# STM32_SIM800C.net
KiCad netlist of a schematic drawn in Altium Designer
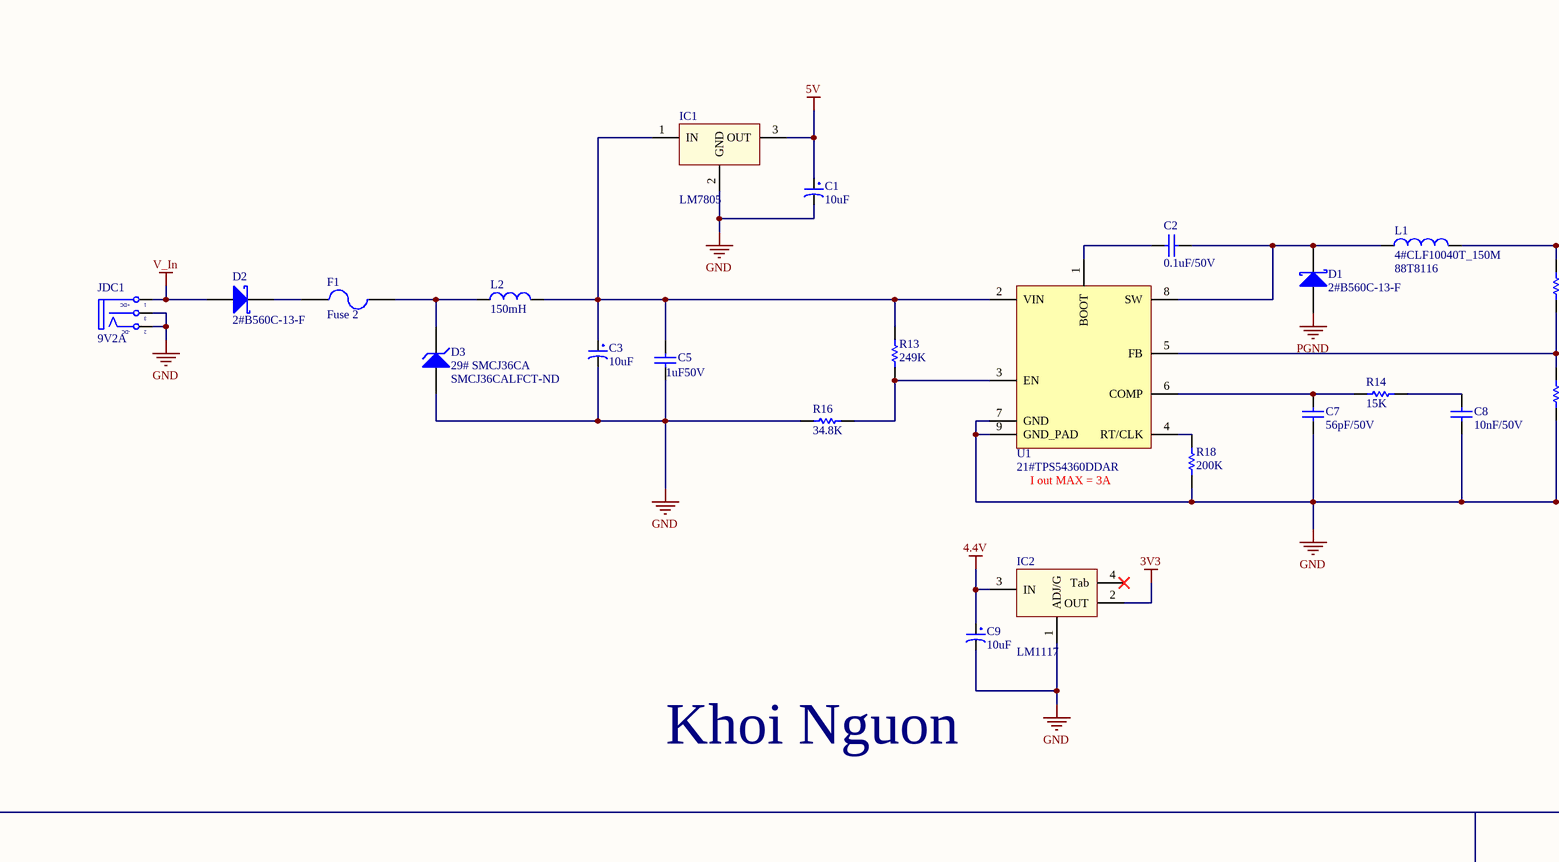
[diagram p0: STM32_SIM800C.SchDoc, top left]
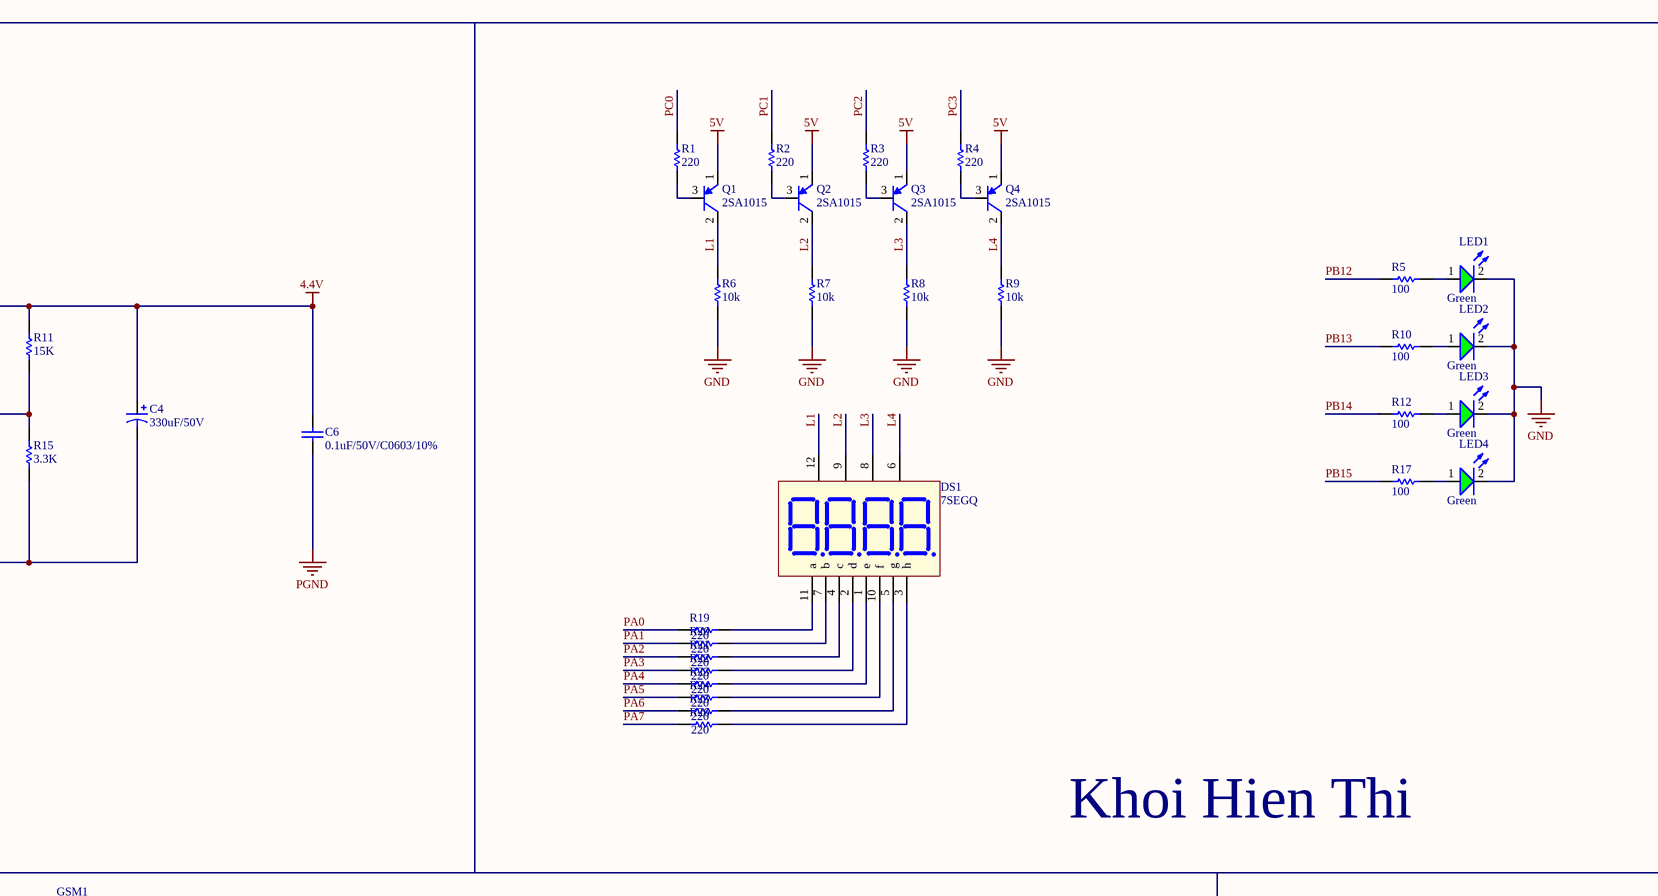
[diagram p1: STM32_SIM800C.SchDoc, top right]
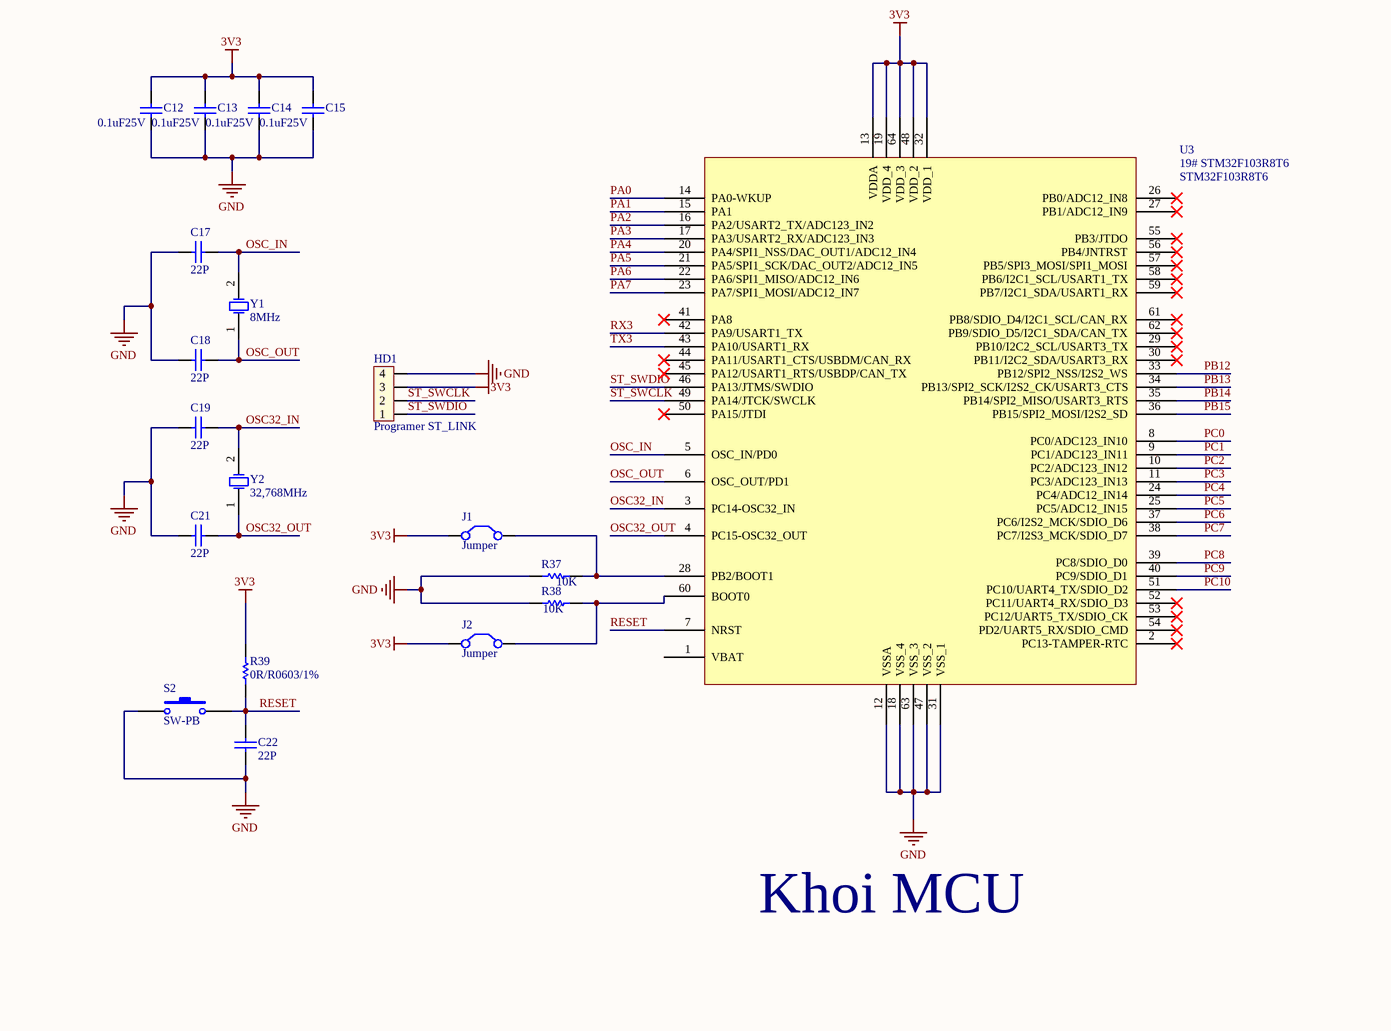
[diagram p2: STM32_SIM800C.SchDoc, bottom left]
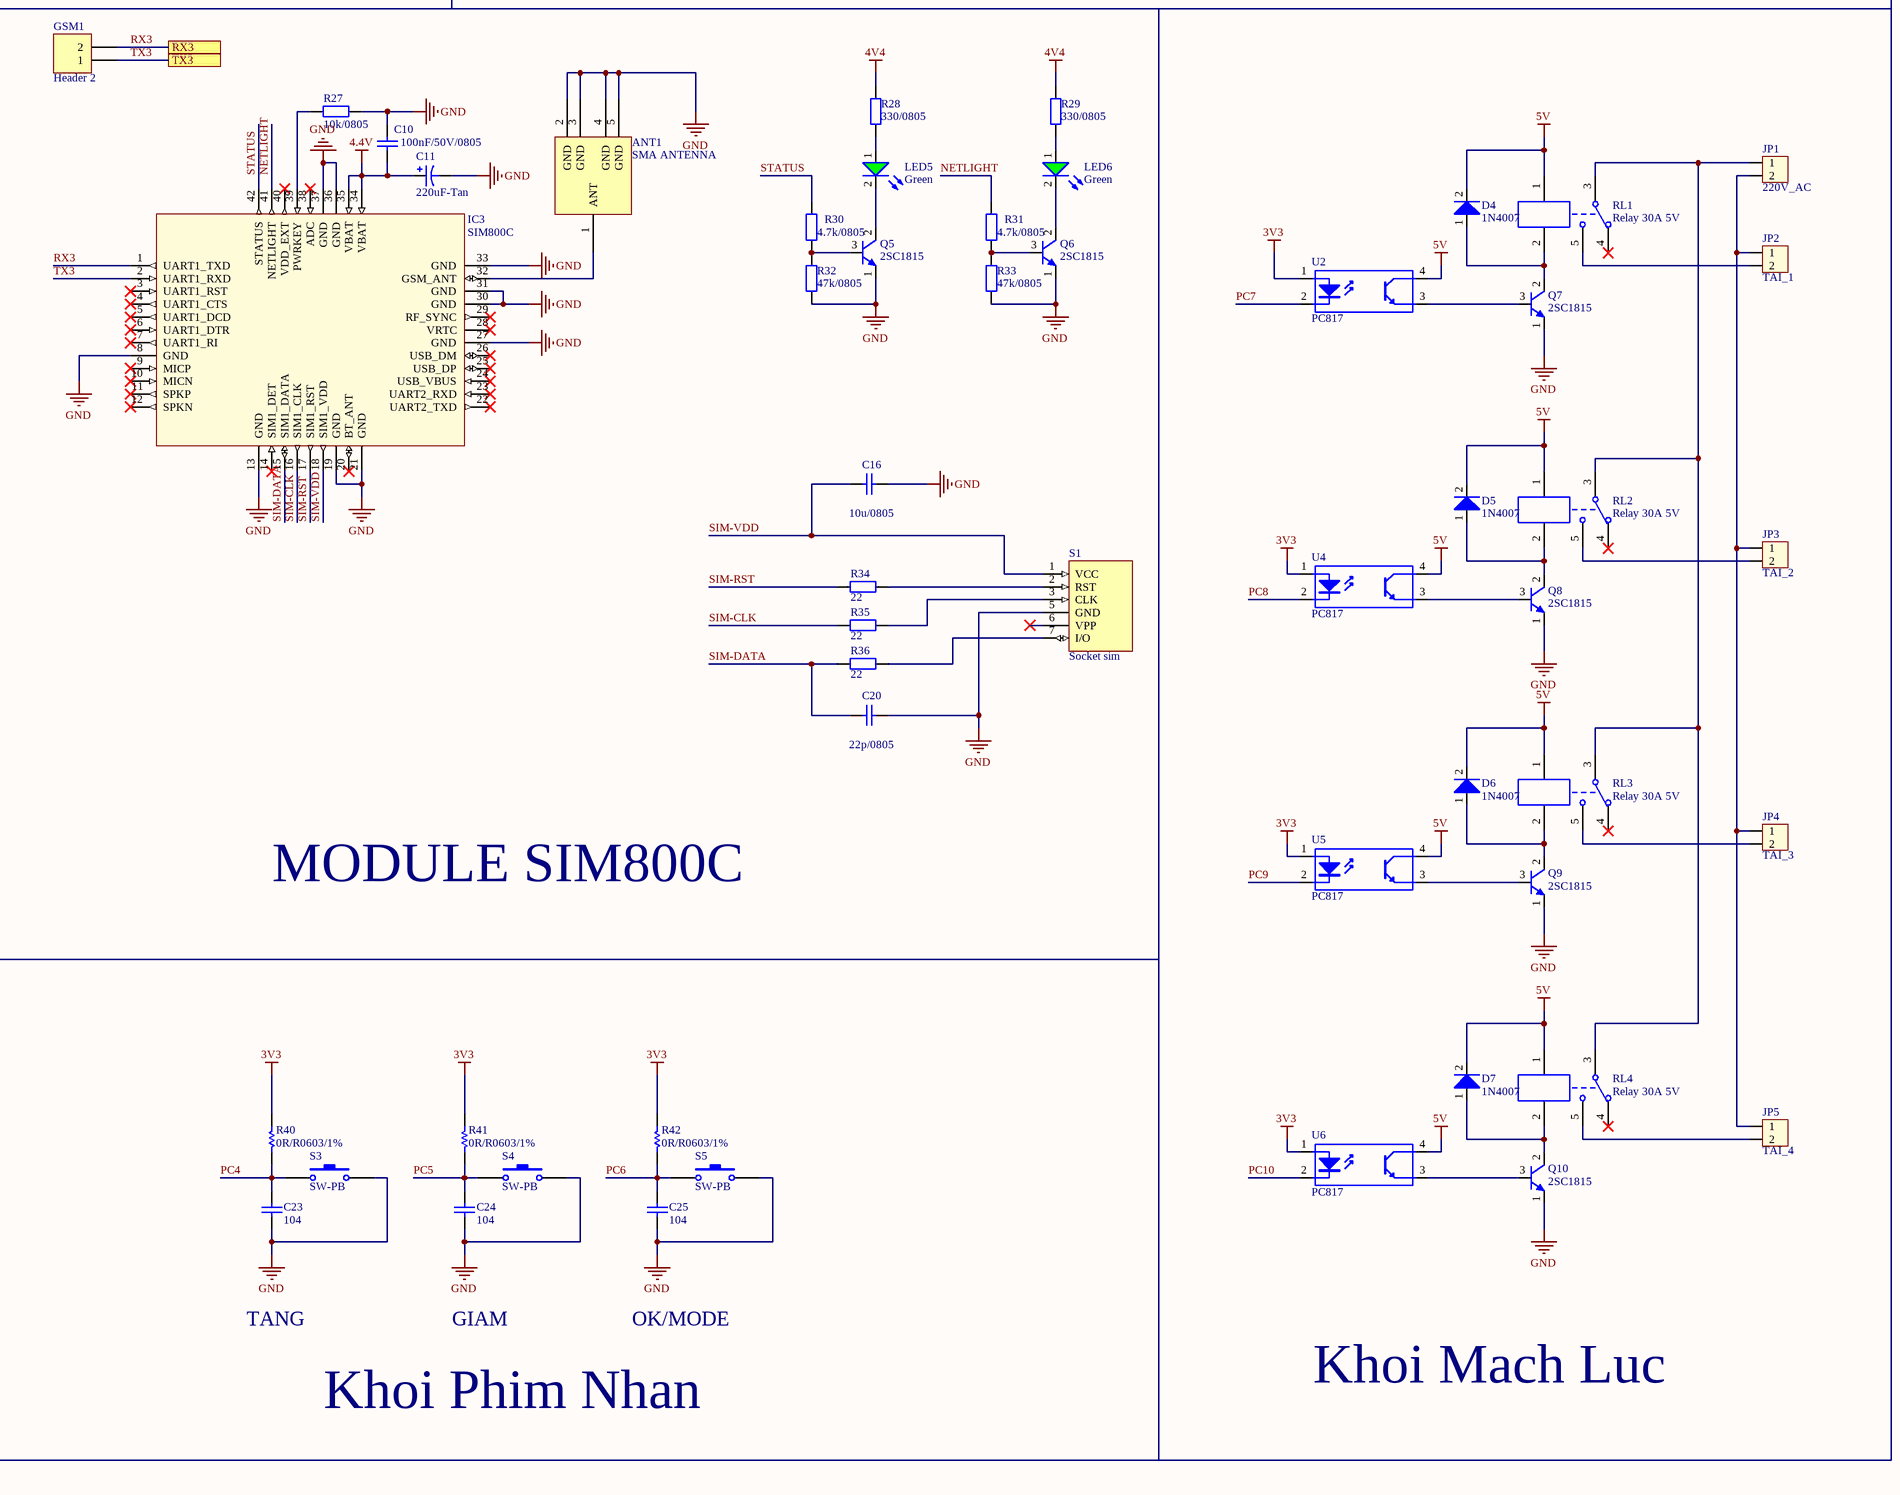
[diagram p3: STM32_SIM800C.SchDoc, bottom right]

(export (version "E")
  (design (tool "Eeschema 10.0.6"))
  (components
    (comp (ref "ANT1")
      (value "SMA ANTENNA")
      (footprint "du an mau 1:ANT-SMA-ST-F")
      (libsource (lib "Air_System_lib") (part "SMA ANTENNA"))
    )
    (comp (ref "C1")
      (value "10uF")
      (footprint "CP1/2")
      (description "Cap P  0,1uF < 22uF , 16 - 50V")
      (libsource (lib "lpson") (part "CP1"))
    )
    (comp (ref "C2")
      (value "0.1uF/50V")
      (footprint "Cap Ceramic 0603 SMD")
      (description "CAP CER 0.1UF 50V 10% X7R 0603")
      (fields
        (field (name "MANUFACTURER") "Murata Electronics North America")
        (field (name "MANUFACTURER PART NUMBER") "GRM188R71H104KA93D")
      )
      (libsource (lib "GSHT_181013") (part "0.1uF/50V/C0603/10%"))
    )
    (comp (ref "C3")
      (value "10uF")
      (footprint "CP1/2")
      (description "Cap P  0,1uF < 22uF , 16 - 50V")
      (libsource (lib "lpson") (part "CP1"))
    )
    (comp (ref "C4")
      (value "330uF/50V")
      (footprint "CAP ALU CASE G SMD")
      (description "CAP ALU 330UF 20% 50V SMD")
      (fields
        (field (name "MANUFACTURER") "Nichicon")
        (field (name "MANUFACTURER PART NUMBER") "UPW1J331MHD")
      )
      (libsource (lib "GSHT_181013") (part "330uF/50V/ALU12.5X20mm/20%/7000Hrs"))
    )
    (comp (ref "C5")
      (value "1uF50V")
      (footprint "Cap Ceramic 0603 SMD")
      (description "CAP CER 0.1UF 50V 10% X7R 0603")
      (fields
        (field (name "MANUFACTURER") "Murata Electronics North America")
        (field (name "MANUFACTURER PART NUMBER") "GRM188R71H104KA93D")
      )
      (libsource (lib "lpson") (part "0.1uF/50V/C0603/10%"))
    )
    (comp (ref "C6")
      (value "0.1uF/50V/C0603/10%")
      (footprint "Cap Ceramic 0603 SMD")
      (description "CAP CER 0.1UF 50V 10% X7R 0603")
      (fields
        (field (name "MANUFACTURER") "Murata Electronics North America")
        (field (name "MANUFACTURER PART NUMBER") "GRM188R71H104KA93D")
      )
      (libsource (lib "GSHT_181013") (part "0.1uF/50V/C0603/10%"))
    )
    (comp (ref "C7")
      (value "56pF/50V")
      (footprint "Cap Ceramic 0603 SMD")
      (description "Cap Ceramic 56pF 50V C0G 5% SMD 0603 125C Paper T/R")
      (fields
        (field (name "MANUFACTURER") "Samsung")
        (field (name "MANUFACTURER PART NUMBER") "CL10C560JB8NNNC")
      )
      (libsource (lib "GSHT_181013") (part "56pF/50V/C0603/5%"))
    )
    (comp (ref "C8")
      (value "10nF/50V")
      (footprint "Cap Ceramic 0603 SMD")
      (description "CAP CER 10000PF 50V X7R 0603")
      (fields
        (field (name "MANUFACTURER") "Murata Electronics North America")
        (field (name "MANUFACTURER PART NUMBER") "GRM188R71H103KA01D")
      )
      (libsource (lib "GSHT_181013") (part "10nF/50V/C0603/10%"))
    )
    (comp (ref "C9")
      (value "10uF")
      (footprint "CP1/2")
      (description "Cap P  0,1uF < 22uF , 16 - 50V")
      (libsource (lib "lpson") (part "CP1"))
    )
    (comp (ref "C10")
      (value "100nF/50V/0805")
      (footprint "C0805-2012")
      (fields (field (name "PUBLISHER") "Altium Limited"))
      (libsource (lib "NBBLib 14-03-2012") (part "CapSMD"))
    )
    (comp (ref "C11")
      (value "220uF-Tan")
      (footprint "CAP_TANTA_10UF_35V")
      (libsource (lib "Air_System_lib") (part "CAP1210-Tan"))
    )
    (comp (ref "C12")
      (value "0.1uF25V")
      (footprint "Cap Ceramic 0603 SMD")
      (description "CAP CER 0.1UF 50V 10% X7R 0603")
      (fields
        (field (name "MANUFACTURER") "Murata Electronics North America")
        (field (name "MANUFACTURER PART NUMBER") "GRM188R71H104KA93D")
      )
      (libsource (lib "lpson") (part "0.1uF/50V/C0603/10%"))
    )
    (comp (ref "C13")
      (value "0.1uF25V")
      (footprint "Cap Ceramic 0603 SMD")
      (description "CAP CER 0.1UF 50V 10% X7R 0603")
      (fields
        (field (name "MANUFACTURER") "Murata Electronics North America")
        (field (name "MANUFACTURER PART NUMBER") "GRM188R71H104KA93D")
      )
      (libsource (lib "lpson") (part "0.1uF/50V/C0603/10%"))
    )
    (comp (ref "C14")
      (value "0.1uF25V")
      (footprint "Cap Ceramic 0603 SMD")
      (description "CAP CER 0.1UF 50V 10% X7R 0603")
      (fields
        (field (name "MANUFACTURER") "Murata Electronics North America")
        (field (name "MANUFACTURER PART NUMBER") "GRM188R71H104KA93D")
      )
      (libsource (lib "lpson") (part "0.1uF/50V/C0603/10%"))
    )
    (comp (ref "C15")
      (value "0.1uF25V")
      (footprint "Cap Ceramic 0603 SMD")
      (description "CAP CER 0.1UF 50V 10% X7R 0603")
      (fields
        (field (name "MANUFACTURER") "Murata Electronics North America")
        (field (name "MANUFACTURER PART NUMBER") "GRM188R71H104KA93D")
      )
      (libsource (lib "lpson") (part "0.1uF/50V/C0603/10%"))
    )
    (comp (ref "C16")
      (value "10u/0805")
      (footprint "C0805-2012")
      (description "Capacitor")
      (fields (field (name "PUBLISHER") "Altium Limited"))
      (libsource (lib "NBBLib 14-03-2012") (part "CapSMD"))
    )
    (comp (ref "C17")
      (value "22P")
      (footprint "Cap Ceramic 0603 SMD")
      (description "CAP CER 0.1UF 50V 10% X7R 0603")
      (fields
        (field (name "MANUFACTURER") "Murata Electronics North America")
        (field (name "MANUFACTURER PART NUMBER") "GRM188R71H104KA93D")
      )
      (libsource (lib "lpson") (part "0.1uF/50V/C0603/10%"))
    )
    (comp (ref "C18")
      (value "22P")
      (footprint "Cap Ceramic 0603 SMD")
      (description "CAP CER 0.1UF 50V 10% X7R 0603")
      (fields
        (field (name "MANUFACTURER") "Murata Electronics North America")
        (field (name "MANUFACTURER PART NUMBER") "GRM188R71H104KA93D")
      )
      (libsource (lib "lpson") (part "0.1uF/50V/C0603/10%"))
    )
    (comp (ref "C19")
      (value "22P")
      (footprint "Cap Ceramic 0603 SMD")
      (description "CAP CER 0.1UF 50V 10% X7R 0603")
      (fields
        (field (name "MANUFACTURER") "Murata Electronics North America")
        (field (name "MANUFACTURER PART NUMBER") "GRM188R71H104KA93D")
      )
      (libsource (lib "lpson") (part "0.1uF/50V/C0603/10%"))
    )
    (comp (ref "C20")
      (value "22p/0805")
      (footprint "C0805-2012")
      (description "Capacitor")
      (fields (field (name "PUBLISHER") "Altium Limited"))
      (libsource (lib "NBBLib 14-03-2012") (part "CapSMD"))
    )
    (comp (ref "C21")
      (value "22P")
      (footprint "Cap Ceramic 0603 SMD")
      (description "CAP CER 0.1UF 50V 10% X7R 0603")
      (fields
        (field (name "MANUFACTURER") "Murata Electronics North America")
        (field (name "MANUFACTURER PART NUMBER") "GRM188R71H104KA93D")
      )
      (libsource (lib "lpson") (part "0.1uF/50V/C0603/10%"))
    )
    (comp (ref "C22")
      (value "22P")
      (footprint "Cap Ceramic 0603 SMD")
      (description "CAP CER 0.1UF 50V 10% X7R 0603")
      (fields
        (field (name "MANUFACTURER") "Murata Electronics North America")
        (field (name "MANUFACTURER PART NUMBER") "GRM188R71H104KA93D")
      )
      (libsource (lib "lpson") (part "0.1uF/50V/C0603/10%"))
    )
    (comp (ref "C23")
      (value "104")
      (footprint "Cap Ceramic 0603 SMD")
      (description "CAP CER 0.1UF 50V 10% X7R 0603")
      (fields
        (field (name "MANUFACTURER") "Murata Electronics North America")
        (field (name "MANUFACTURER PART NUMBER") "GRM188R71H104KA93D")
      )
      (libsource (lib "lpson") (part "0.1uF/50V/C0603/10%"))
    )
    (comp (ref "C24")
      (value "104")
      (footprint "Cap Ceramic 0603 SMD")
      (description "CAP CER 0.1UF 50V 10% X7R 0603")
      (fields
        (field (name "MANUFACTURER") "Murata Electronics North America")
        (field (name "MANUFACTURER PART NUMBER") "GRM188R71H104KA93D")
      )
      (libsource (lib "lpson") (part "0.1uF/50V/C0603/10%"))
    )
    (comp (ref "C25")
      (value "104")
      (footprint "Cap Ceramic 0603 SMD")
      (description "CAP CER 0.1UF 50V 10% X7R 0603")
      (fields
        (field (name "MANUFACTURER") "Murata Electronics North America")
        (field (name "MANUFACTURER PART NUMBER") "GRM188R71H104KA93D")
      )
      (libsource (lib "lpson") (part "0.1uF/50V/C0603/10%"))
    )
    (comp (ref "D1")
      (value "2#B560C-13-F")
      (footprint "2# B560C")
      (description "DIODE SCHOTTKY 60V 5A SMC")
      (fields (field (name "MANUFACTURER") "Diodes") (field (name "MANUFACTURER PART NUMBER") "B560C-13-F"))
      (libsource (lib "GSHT_181013") (part "2#B560C-13-F"))
    )
    (comp (ref "D2")
      (value "2#B560C-13-F")
      (footprint "2# B560C")
      (description "DIODE SCHOTTKY 60V 5A SMC")
      (fields (field (name "MANUFACTURER") "Diodes") (field (name "MANUFACTURER PART NUMBER") "B560C-13-F"))
      (libsource (lib "lpson") (part "2#B560C-13-F"))
    )
    (comp (ref "D3")
      (value "29# SMCJ36CA")
      (footprint "29# diode SMCJ36A")
      (description "TVS DIODE 36VWM 58.1VC SMC")
      (fields
        (field (name "MANUFACTURER") "Littelfuse")
        (field (name "MANUFACTURER PART NUMBER") "SMCJ36CA")
        (field (name "SUPPLIER PART NUMBER 1") "SMCJ36CALFCT-ND")
      )
      (libsource (lib "GSHT_181013") (part "29# SMCJ36CA"))
    )
    (comp (ref "D4")
      (value "1N4007")
      (footprint "1N4007")
      (description "Diode LS 1A 1000V DO-41")
      (libsource (lib "lpson") (part "1N4007"))
    )
    (comp (ref "D5")
      (value "1N4007")
      (footprint "1N4007")
      (description "Diode LS 1A 1000V DO-41")
      (libsource (lib "lpson") (part "1N4007"))
    )
    (comp (ref "D6")
      (value "1N4007")
      (footprint "1N4007")
      (description "Diode LS 1A 1000V DO-41")
      (libsource (lib "lpson") (part "1N4007"))
    )
    (comp (ref "D7")
      (value "1N4007")
      (footprint "1N4007")
      (description "Diode LS 1A 1000V DO-41")
      (libsource (lib "lpson") (part "1N4007"))
    )
    (comp (ref "DS1")
      (value "7SEGQ")
      (footprint "7SEGQ")
      (description "Four 7 Seg Dipslay")
      (libsource (lib "lpson") (part "LED7Q"))
    )
    (comp (ref "F1")
      (value "Fuse 2")
      (footprint "PIN-W2/E2.8")
      (description "Fuse")
      (fields (field (name "PUBLISHER") "Altium Limited"))
      (libsource (lib "lpson") (part "Fuse 2"))
    )
    (comp (ref "GSM1")
      (value "Header 2")
      (footprint "Header_2")
      (description "Header, 2-Pin")
      (fields (field (name "PUBLISHER") "Altium Limited"))
      (libsource (lib "NBBLib 14-03-2012") (part "Header 2"))
    )
    (comp (ref "HD1")
      (value "Programer ST_LINK")
      (footprint "Header_4")
      (description "Header 4")
      (libsource (lib "lpson") (part "Header4"))
    )
    (comp (ref "IC1")
      (value "LM7805")
      (footprint "QTO-220")
      (description "On ap +, from + 5 to + 24VDC")
      (libsource (lib "lpson") (part "LM78xx"))
    )
    (comp (ref "IC2")
      (value "LM1117")
      (footprint "SOT223-4N")
      (description "3v3")
      (libsource (lib "lpson") (part "LM1117"))
    )
    (comp (ref "IC3")
      (value "SIM800C")
      (footprint "SIM800C")
      (description "SIM800C V1.00")
      (libsource (lib "LIEMTHANH_LIB") (part "SIM800C"))
    )
    (comp (ref "J1")
      (value "Jumper")
      (footprint "Header_2")
      (description "Jumper Wire")
      (fields (field (name "PUBLISHER") "Altium Limited"))
      (libsource (lib "lpson") (part "Jumper"))
    )
    (comp (ref "J2")
      (value "Jumper")
      (footprint "Header_2")
      (description "Jumper Wire")
      (fields (field (name "PUBLISHER") "Altium Limited"))
      (libsource (lib "lpson") (part "Jumper"))
    )
    (comp (ref "JDC1")
      (value "9V2A")
      (footprint "DC-IN")
      (description "Jac DC input")
      (libsource (lib "lpson") (part "DCIN"))
    )
    (comp (ref "JP1")
      (value "220V_AC")
      (footprint "DOMINO_OSTTC_2P")
      (description "Connector 2")
      (libsource (lib "lpson") (part "Con2_1"))
    )
    (comp (ref "JP2")
      (value "TAI_1")
      (footprint "DOMINO_OSTTC_2P")
      (description "Connector 2")
      (libsource (lib "lpson") (part "Con2_1"))
    )
    (comp (ref "JP3")
      (value "TAI_2")
      (footprint "DOMINO_OSTTC_2P")
      (description "Connector 2")
      (libsource (lib "lpson") (part "Con2_1"))
    )
    (comp (ref "JP4")
      (value "TAI_3")
      (footprint "DOMINO_OSTTC_2P")
      (description "Connector 2")
      (libsource (lib "lpson") (part "Con2_1"))
    )
    (comp (ref "JP5")
      (value "TAI_4")
      (footprint "DOMINO_OSTTC_2P")
      (description "Connector 2")
      (libsource (lib "lpson") (part "Con2_1"))
    )
    (comp (ref "L1")
      (value "4#CLF10040T_150M")
      (footprint "4# clf10040XX")
      (description "FIXED IND 15uH 3.2A 40 MOHM (10.0×9.7×3.8)")
      (fields (field (name "SUPPLIER PART NUMBER 1") "88T8116"))
      (libsource (lib "GSHT_181013") (part "4#CLF10040T_150M"))
    )
    (comp (ref "L2")
      (value "150mH")
      (footprint "L/0.4")
      (description "Inductor")
      (libsource (lib "lpson") (part "L1"))
    )
    (comp (ref "LED1")
      (value "Green")
      (footprint "LED5G")
      (description "LED Green 20mA 2.2V 5mm")
      (fields (field (name "Comment") "LT0054"))
      (libsource (lib "lpson") (part "LT0054"))
    )
    (comp (ref "LED2")
      (value "Green")
      (footprint "LED5G")
      (description "LED Green 20mA 2.2V 5mm")
      (fields (field (name "Comment") "LT0054"))
      (libsource (lib "lpson") (part "LT0054"))
    )
    (comp (ref "LED3")
      (value "Green")
      (footprint "LED5G")
      (description "LED Green 20mA 2.2V 5mm")
      (fields (field (name "Comment") "LT0054"))
      (libsource (lib "lpson") (part "LT0054"))
    )
    (comp (ref "LED4")
      (value "Green")
      (footprint "LED5G")
      (description "LED Green 20mA 2.2V 5mm")
      (fields (field (name "Comment") "LT0054"))
      (libsource (lib "lpson") (part "LT0054"))
    )
    (comp (ref "LED5")
      (value "Green")
      (footprint "LED5G")
      (description "LED Green 20mA 2.2V 5mm")
      (fields (field (name "Comment") "LT0054"))
      (libsource (lib "lpson") (part "LT0054"))
    )
    (comp (ref "LED6")
      (value "Green")
      (footprint "LED5G")
      (description "LED Green 20mA 2.2V 5mm")
      (fields (field (name "Comment") "LT0054"))
      (libsource (lib "lpson") (part "LT0054"))
    )
    (comp (ref "Q1")
      (value "2SA1015")
      (footprint "2SA1015")
      (description "Trans PNP -50V -150mA TO-92")
      (libsource (lib "lpson") (part "2SA1015"))
    )
    (comp (ref "Q2")
      (value "2SA1015")
      (footprint "2SA1015")
      (description "Trans PNP -50V -150mA TO-92")
      (libsource (lib "lpson") (part "2SA1015"))
    )
    (comp (ref "Q3")
      (value "2SA1015")
      (footprint "2SA1015")
      (description "Trans PNP -50V -150mA TO-92")
      (libsource (lib "lpson") (part "2SA1015"))
    )
    (comp (ref "Q4")
      (value "2SA1015")
      (footprint "2SA1015")
      (description "Trans PNP -50V -150mA TO-92")
      (libsource (lib "lpson") (part "2SA1015"))
    )
    (comp (ref "Q5")
      (value "2SC1815")
      (footprint "2SC1815")
      (description "Trans NPN 50V 150mA TO-92")
      (libsource (lib "lpson") (part "2SC1815"))
    )
    (comp (ref "Q6")
      (value "2SC1815")
      (footprint "2SC1815")
      (description "Trans NPN 50V 150mA TO-92")
      (libsource (lib "lpson") (part "2SC1815"))
    )
    (comp (ref "Q7")
      (value "2SC1815")
      (footprint "2SC1815")
      (description "Trans NPN 50V 150mA TO-92")
      (libsource (lib "lpson") (part "2SC1815"))
    )
    (comp (ref "Q8")
      (value "2SC1815")
      (footprint "2SC1815")
      (description "Trans NPN 50V 150mA TO-92")
      (libsource (lib "lpson") (part "2SC1815"))
    )
    (comp (ref "Q9")
      (value "2SC1815")
      (footprint "2SC1815")
      (description "Trans NPN 50V 150mA TO-92")
      (libsource (lib "lpson") (part "2SC1815"))
    )
    (comp (ref "Q10")
      (value "2SC1815")
      (footprint "2SC1815")
      (description "Trans NPN 50V 150mA TO-92")
      (libsource (lib "lpson") (part "2SC1815"))
    )
    (comp (ref "R1")
      (value "220")
      (footprint "Res 0603 SMD")
      (description "RES SMD 10K OHM 1% 1/10W 0603")
      (fields
        (field (name "MANUFACTURER") "Yageo")
        (field (name "MANUFACTURER PART NUMBER") "RC0603FR-0710KL")
      )
      (libsource (lib "lpson") (part "10K/R0603/1%"))
    )
    (comp (ref "R2")
      (value "220")
      (footprint "Res 0603 SMD")
      (description "RES SMD 10K OHM 1% 1/10W 0603")
      (fields
        (field (name "MANUFACTURER") "Yageo")
        (field (name "MANUFACTURER PART NUMBER") "RC0603FR-0710KL")
      )
      (libsource (lib "lpson") (part "10K/R0603/1%"))
    )
    (comp (ref "R3")
      (value "220")
      (footprint "Res 0603 SMD")
      (description "RES SMD 10K OHM 1% 1/10W 0603")
      (fields
        (field (name "MANUFACTURER") "Yageo")
        (field (name "MANUFACTURER PART NUMBER") "RC0603FR-0710KL")
      )
      (libsource (lib "lpson") (part "10K/R0603/1%"))
    )
    (comp (ref "R4")
      (value "220")
      (footprint "Res 0603 SMD")
      (description "RES SMD 10K OHM 1% 1/10W 0603")
      (fields
        (field (name "MANUFACTURER") "Yageo")
        (field (name "MANUFACTURER PART NUMBER") "RC0603FR-0710KL")
      )
      (libsource (lib "lpson") (part "10K/R0603/1%"))
    )
    (comp (ref "R5")
      (value "100")
      (footprint "Res 0603 SMD")
      (description "RES SMD 10K OHM 1% 1/10W 0603")
      (fields
        (field (name "MANUFACTURER") "Yageo")
        (field (name "MANUFACTURER PART NUMBER") "RC0603FR-0710KL")
      )
      (libsource (lib "lpson") (part "10K/R0603/1%"))
    )
    (comp (ref "R6")
      (value "10k")
      (footprint "Res 0603 SMD")
      (description "RES SMD 10K OHM 1% 1/10W 0603")
      (fields
        (field (name "MANUFACTURER") "Yageo")
        (field (name "MANUFACTURER PART NUMBER") "RC0603FR-0710KL")
      )
      (libsource (lib "lpson") (part "10K/R0603/1%"))
    )
    (comp (ref "R7")
      (value "10k")
      (footprint "Res 0603 SMD")
      (description "RES SMD 10K OHM 1% 1/10W 0603")
      (fields
        (field (name "MANUFACTURER") "Yageo")
        (field (name "MANUFACTURER PART NUMBER") "RC0603FR-0710KL")
      )
      (libsource (lib "lpson") (part "10K/R0603/1%"))
    )
    (comp (ref "R8")
      (value "10k")
      (footprint "Res 0603 SMD")
      (description "RES SMD 10K OHM 1% 1/10W 0603")
      (fields
        (field (name "MANUFACTURER") "Yageo")
        (field (name "MANUFACTURER PART NUMBER") "RC0603FR-0710KL")
      )
      (libsource (lib "lpson") (part "10K/R0603/1%"))
    )
    (comp (ref "R9")
      (value "10k")
      (footprint "Res 0603 SMD")
      (description "RES SMD 10K OHM 1% 1/10W 0603")
      (fields
        (field (name "MANUFACTURER") "Yageo")
        (field (name "MANUFACTURER PART NUMBER") "RC0603FR-0710KL")
      )
      (libsource (lib "lpson") (part "10K/R0603/1%"))
    )
    (comp (ref "R10")
      (value "100")
      (footprint "Res 0603 SMD")
      (description "RES SMD 10K OHM 1% 1/10W 0603")
      (fields
        (field (name "MANUFACTURER") "Yageo")
        (field (name "MANUFACTURER PART NUMBER") "RC0603FR-0710KL")
      )
      (libsource (lib "lpson") (part "10K/R0603/1%"))
    )
    (comp (ref "R11")
      (value "15K")
      (footprint "Res 0603 SMD")
      (description "RES SMD 15K OHM 1% 1/10W 0603")
      (fields
        (field (name "MANUFACTURER") "Yageo")
        (field (name "MANUFACTURER PART NUMBER") "RC0603FR-0715KL")
      )
      (libsource (lib "GSHT_181013") (part "15K/R0603/1%"))
    )
    (comp (ref "R12")
      (value "100")
      (footprint "Res 0603 SMD")
      (description "RES SMD 10K OHM 1% 1/10W 0603")
      (fields
        (field (name "MANUFACTURER") "Yageo")
        (field (name "MANUFACTURER PART NUMBER") "RC0603FR-0710KL")
      )
      (libsource (lib "lpson") (part "10K/R0603/1%"))
    )
    (comp (ref "R13")
      (value "249K")
      (footprint "Res 0805 SMD")
      (description "RES SMD 249K OHM 1% 1/10W 0805")
      (fields
        (field (name "MANUFACTURER") "Yageo")
        (field (name "MANUFACTURER PART NUMBER") "RC0603FR-07249KL")
      )
      (libsource (lib "GSHT_181013") (part "249K/R0805/1%"))
    )
    (comp (ref "R14")
      (value "15K")
      (footprint "Res 0603 SMD")
      (description "RES SMD 15K OHM 1% 1/10W 0603")
      (fields
        (field (name "MANUFACTURER") "Yageo")
        (field (name "MANUFACTURER PART NUMBER") "RC0603FR-0715KL")
      )
      (libsource (lib "GSHT_181013") (part "15K/R0603/1%"))
    )
    (comp (ref "R15")
      (value "3.3K")
      (footprint "Cap Ceramic 0603 SMD")
      (description "RES SMD 3.3K OHM 1% 1/10W 0603")
      (fields
        (field (name "MANUFACTURER") "Yageo")
        (field (name "MANUFACTURER PART NUMBER") "RC0603FR-073K3L")
      )
      (libsource (lib "GSHT_181013") (part "3.3K/R0603/1%"))
    )
    (comp (ref "R16")
      (value "34.8K")
      (footprint "Res 0805 SMD")
      (description "Thick Film Resistors - SMD 34.8K OHM 1% 0805")
      (fields
        (field (name "MANUFACTURER") "Yageo")
        (field (name "MANUFACTURER PART NUMBER") "RC0603FR-0734K8L")
      )
      (libsource (lib "GSHT_181013") (part "34.8K/R0805/1%"))
    )
    (comp (ref "R17")
      (value "100")
      (footprint "Res 0603 SMD")
      (description "RES SMD 10K OHM 1% 1/10W 0603")
      (fields
        (field (name "MANUFACTURER") "Yageo")
        (field (name "MANUFACTURER PART NUMBER") "RC0603FR-0710KL")
      )
      (libsource (lib "lpson") (part "10K/R0603/1%"))
    )
    (comp (ref "R18")
      (value "200K")
      (footprint "Res 0603 SMD")
      (description "RES SMD 200K OHM 1% 1/10W 0603")
      (fields
        (field (name "MANUFACTURER") "Yageo")
        (field (name "MANUFACTURER PART NUMBER") "RC0603FR-07200KL")
      )
      (libsource (lib "GSHT_181013") (part "200K/R0603/1%"))
    )
    (comp (ref "R19")
      (value "220")
      (footprint "Res 0603 SMD")
      (description "RES SMD 10K OHM 1% 1/10W 0603")
      (fields
        (field (name "MANUFACTURER") "Yageo")
        (field (name "MANUFACTURER PART NUMBER") "RC0603FR-0710KL")
      )
      (libsource (lib "lpson") (part "10K/R0603/1%"))
    )
    (comp (ref "R20")
      (value "220")
      (footprint "Res 0603 SMD")
      (description "RES SMD 10K OHM 1% 1/10W 0603")
      (fields
        (field (name "MANUFACTURER") "Yageo")
        (field (name "MANUFACTURER PART NUMBER") "RC0603FR-0710KL")
      )
      (libsource (lib "lpson") (part "10K/R0603/1%"))
    )
    (comp (ref "R21")
      (value "220")
      (footprint "Res 0603 SMD")
      (description "RES SMD 10K OHM 1% 1/10W 0603")
      (fields
        (field (name "MANUFACTURER") "Yageo")
        (field (name "MANUFACTURER PART NUMBER") "RC0603FR-0710KL")
      )
      (libsource (lib "lpson") (part "10K/R0603/1%"))
    )
    (comp (ref "R22")
      (value "220")
      (footprint "Res 0603 SMD")
      (description "RES SMD 10K OHM 1% 1/10W 0603")
      (fields
        (field (name "MANUFACTURER") "Yageo")
        (field (name "MANUFACTURER PART NUMBER") "RC0603FR-0710KL")
      )
      (libsource (lib "lpson") (part "10K/R0603/1%"))
    )
    (comp (ref "R23")
      (value "220")
      (footprint "Res 0603 SMD")
      (description "RES SMD 10K OHM 1% 1/10W 0603")
      (fields
        (field (name "MANUFACTURER") "Yageo")
        (field (name "MANUFACTURER PART NUMBER") "RC0603FR-0710KL")
      )
      (libsource (lib "lpson") (part "10K/R0603/1%"))
    )
    (comp (ref "R24")
      (value "220")
      (footprint "Res 0603 SMD")
      (description "RES SMD 10K OHM 1% 1/10W 0603")
      (fields
        (field (name "MANUFACTURER") "Yageo")
        (field (name "MANUFACTURER PART NUMBER") "RC0603FR-0710KL")
      )
      (libsource (lib "lpson") (part "10K/R0603/1%"))
    )
    (comp (ref "R25")
      (value "220")
      (footprint "Res 0603 SMD")
      (description "RES SMD 10K OHM 1% 1/10W 0603")
      (fields
        (field (name "MANUFACTURER") "Yageo")
        (field (name "MANUFACTURER PART NUMBER") "RC0603FR-0710KL")
      )
      (libsource (lib "lpson") (part "10K/R0603/1%"))
    )
    (comp (ref "R26")
      (value "220")
      (footprint "Res 0603 SMD")
      (description "RES SMD 10K OHM 1% 1/10W 0603")
      (fields
        (field (name "MANUFACTURER") "Yageo")
        (field (name "MANUFACTURER PART NUMBER") "RC0603FR-0710KL")
      )
      (libsource (lib "lpson") (part "10K/R0603/1%"))
    )
    (comp (ref "R27")
      (value "10k/0805")
      (footprint "RESC2012(0805)")
      (description "Resistor SMD 0805")
      (fields (field (name "PUBLISHER") "Altium Limited"))
      (libsource (lib "NBBLib 14-03-2012") (part "R0805"))
    )
    (comp (ref "R28")
      (value "330/0805")
      (footprint "RESC2012(0805)")
      (description "Resistor SMD 0805")
      (fields (field (name "Comment") "R0805") (field (name "PUBLISHER") "Altium Limited"))
      (libsource (lib "") (part "R0805_1"))
    )
    (comp (ref "R29")
      (value "330/0805")
      (footprint "RESC2012(0805)")
      (description "Resistor SMD 0805")
      (fields (field (name "Comment") "R0805") (field (name "PUBLISHER") "Altium Limited"))
      (libsource (lib "") (part "R0805_1"))
    )
    (comp (ref "R30")
      (value "4.7k/0805")
      (footprint "RESC2012(0805)")
      (description "Resistor SMD 0805")
      (fields (field (name "Comment") "R0805") (field (name "PUBLISHER") "Altium Limited"))
      (libsource (lib "") (part "R0805_1"))
    )
    (comp (ref "R31")
      (value "4.7k/0805")
      (footprint "RESC2012(0805)")
      (description "Resistor SMD 0805")
      (fields (field (name "Comment") "R0805") (field (name "PUBLISHER") "Altium Limited"))
      (libsource (lib "") (part "R0805_1"))
    )
    (comp (ref "R32")
      (value "47k/0805")
      (footprint "RESC2012(0805)")
      (description "Resistor SMD 0805")
      (fields (field (name "Comment") "R0805") (field (name "PUBLISHER") "Altium Limited"))
      (libsource (lib "") (part "R0805_1"))
    )
    (comp (ref "R33")
      (value "47k/0805")
      (footprint "RESC2012(0805)")
      (description "Resistor SMD 0805")
      (fields (field (name "Comment") "R0805") (field (name "PUBLISHER") "Altium Limited"))
      (libsource (lib "") (part "R0805_1"))
    )
    (comp (ref "R34")
      (value "22")
      (footprint "RESC2012(0805)")
      (description "Resistor SMD 0805")
      (fields (field (name "Comment") "R0805") (field (name "PUBLISHER") "Altium Limited"))
      (libsource (lib "NBBLib 14-03-2012") (part "R0805"))
    )
    (comp (ref "R35")
      (value "22")
      (footprint "RESC2012(0805)")
      (description "Resistor SMD 0805")
      (fields (field (name "Comment") "R0805") (field (name "PUBLISHER") "Altium Limited"))
      (libsource (lib "NBBLib 14-03-2012") (part "R0805"))
    )
    (comp (ref "R36")
      (value "22")
      (footprint "RESC2012(0805)")
      (description "Resistor SMD 0805")
      (fields (field (name "Comment") "R0805") (field (name "PUBLISHER") "Altium Limited"))
      (libsource (lib "NBBLib 14-03-2012") (part "R0805"))
    )
    (comp (ref "R37")
      (value "10K")
      (footprint "Res 0603 SMD")
      (description "RES SMD 10K OHM 1% 1/10W 0603")
      (fields
        (field (name "MANUFACTURER") "Yageo")
        (field (name "MANUFACTURER PART NUMBER") "RC0603FR-0710KL")
      )
      (libsource (lib "lpson") (part "10K/R0603/1%"))
    )
    (comp (ref "R38")
      (value "10K")
      (footprint "Res 0603 SMD")
      (description "RES SMD 10K OHM 1% 1/10W 0603")
      (fields
        (field (name "MANUFACTURER") "Yageo")
        (field (name "MANUFACTURER PART NUMBER") "RC0603FR-0710KL")
      )
      (libsource (lib "lpson") (part "10K/R0603/1%"))
    )
    (comp (ref "R39")
      (value "0R/R0603/1%")
      (footprint "Res 0603 SMD")
      (description "RES SMD 10K OHM 1% 1/10W 0603")
      (fields
        (field (name "MANUFACTURER") "Yageo")
        (field (name "MANUFACTURER PART NUMBER") "RC0603FR-0710KL")
      )
      (libsource (lib "lpson") (part "10K/R0603/1%"))
    )
    (comp (ref "R40")
      (value "0R/R0603/1%")
      (footprint "Res 0603 SMD")
      (description "RES SMD 10K OHM 1% 1/10W 0603")
      (fields
        (field (name "MANUFACTURER") "Yageo")
        (field (name "MANUFACTURER PART NUMBER") "RC0603FR-0710KL")
      )
      (libsource (lib "lpson") (part "10K/R0603/1%"))
    )
    (comp (ref "R41")
      (value "0R/R0603/1%")
      (footprint "Res 0603 SMD")
      (description "RES SMD 10K OHM 1% 1/10W 0603")
      (fields
        (field (name "MANUFACTURER") "Yageo")
        (field (name "MANUFACTURER PART NUMBER") "RC0603FR-0710KL")
      )
      (libsource (lib "lpson") (part "10K/R0603/1%"))
    )
    (comp (ref "R42")
      (value "0R/R0603/1%")
      (footprint "Res 0603 SMD")
      (description "RES SMD 10K OHM 1% 1/10W 0603")
      (fields
        (field (name "MANUFACTURER") "Yageo")
        (field (name "MANUFACTURER PART NUMBER") "RC0603FR-0710KL")
      )
      (libsource (lib "lpson") (part "10K/R0603/1%"))
    )
    (comp (ref "RL1")
      (value "Relay 30A 5V")
      (footprint "RL_5V_30A")
      (description "Single-Pole Dual-Throw Relay")
      (fields (field (name "PUBLISHER") "Altium Limited"))
      (libsource (lib "lpson") (part "Relay T9GV5L14-5 30A 5V"))
    )
    (comp (ref "RL2")
      (value "Relay 30A 5V")
      (footprint "RL_5V_30A")
      (description "Single-Pole Dual-Throw Relay")
      (fields (field (name "PUBLISHER") "Altium Limited"))
      (libsource (lib "lpson") (part "Relay T9GV5L14-5 30A 5V"))
    )
    (comp (ref "RL3")
      (value "Relay 30A 5V")
      (footprint "RL_5V_30A")
      (description "Single-Pole Dual-Throw Relay")
      (fields (field (name "PUBLISHER") "Altium Limited"))
      (libsource (lib "lpson") (part "Relay T9GV5L14-5 30A 5V"))
    )
    (comp (ref "RL4")
      (value "Relay 30A 5V")
      (footprint "RL_5V_30A")
      (description "Single-Pole Dual-Throw Relay")
      (fields (field (name "PUBLISHER") "Altium Limited"))
      (libsource (lib "lpson") (part "Relay T9GV5L14-5 30A 5V"))
    )
    (comp (ref "S1")
      (value "Socket sim")
      (footprint "Card Sim")
      (libsource (lib "Air_System_lib") (part "Socket sim"))
    )
    (comp (ref "S2")
      (value "SW-PB")
      (footprint "SPST-2")
      (description "Switch")
      (fields (field (name "PUBLISHER") "Altium Limited"))
      (libsource (lib "lpson") (part "SW-PB"))
    )
    (comp (ref "S3")
      (value "SW-PB")
      (footprint "SPST-2")
      (description "Switch")
      (fields (field (name "PUBLISHER") "Altium Limited"))
      (libsource (lib "lpson") (part "SW-PB"))
    )
    (comp (ref "S4")
      (value "SW-PB")
      (footprint "SPST-2")
      (description "Switch")
      (fields (field (name "PUBLISHER") "Altium Limited"))
      (libsource (lib "lpson") (part "SW-PB"))
    )
    (comp (ref "S5")
      (value "SW-PB")
      (footprint "SPST-2")
      (description "Switch")
      (fields (field (name "PUBLISHER") "Altium Limited"))
      (libsource (lib "lpson") (part "SW-PB"))
    )
    (comp (ref "U1")
      (value "21#TPS54360DDAR")
      (footprint "21# TPS54360")
      (description "Voltage Regulators - Switching Regulators 60 Vin,3.5 A,SD DC-DC Converter")
      (fields
        (field (name "MANUFACTURER") "Texas Instruments")
        (field (name "MANUFACTURER PART NUMBER") "TPS54360DDAR")
      )
      (libsource (lib "GSHT_181013") (part "21#TPS54360DDAR"))
    )
    (comp (ref "U2")
      (value "PC817")
      (footprint "DIP-4")
      (description "4-Pin Phototransistor Optocoupler")
      (fields (field (name "PUBLISHER") "Altium Limited"))
      (libsource (lib "lpson") (part "Optoisolator1"))
    )
    (comp (ref "U3")
      (value "19# STM32F103R8T6")
      (footprint "19# STMF103R8T6")
      (fields
        (field (name "SUPPLIER PART NUMBER 1") "STM32F103R8T6")
        (field (name "PUBLISHER") "Altium Limited")
      )
      (libsource (lib "GSHT_181013") (part "19# STM32F103R8T6"))
    )
    (comp (ref "U4")
      (value "PC817")
      (footprint "DIP-4")
      (description "4-Pin Phototransistor Optocoupler")
      (fields (field (name "PUBLISHER") "Altium Limited"))
      (libsource (lib "lpson") (part "Optoisolator1"))
    )
    (comp (ref "U5")
      (value "PC817")
      (footprint "DIP-4")
      (description "4-Pin Phototransistor Optocoupler")
      (fields (field (name "PUBLISHER") "Altium Limited"))
      (libsource (lib "lpson") (part "Optoisolator1"))
    )
    (comp (ref "U6")
      (value "PC817")
      (footprint "DIP-4")
      (description "4-Pin Phototransistor Optocoupler")
      (fields (field (name "PUBLISHER") "Altium Limited"))
      (libsource (lib "lpson") (part "Optoisolator1"))
    )
    (comp (ref "Y1")
      (value "8MHz")
      (footprint "CRYSTAL")
      (description "Crystal Oscillator")
      (fields (field (name "PUBLISHER") "Altium Limited"))
      (libsource (lib "lpson") (part "XTAL_12MHz"))
    )
    (comp (ref "Y2")
      (value "32,768MHz")
      (footprint "CRYSTAL")
      (description "Crystal Oscillator")
      (fields (field (name "PUBLISHER") "Altium Limited"))
      (libsource (lib "lpson") (part "XTAL_12MHz"))
    )
  )
  (nets
    (net (code "2") (name "/L1") (class "Default")
      (node (ref "DS1") (pin "12") (pinfunction "V1_12") (pintype "passive"))
      (node (ref "Q1") (pin "2") (pinfunction "C_2") (pintype "passive"))
      (node (ref "R6") (pin "2") (pinfunction "2_2") (pintype "passive"))
    )
    (net (code "3") (name "/L2") (class "Default")
      (node (ref "DS1") (pin "9") (pinfunction "V2_9") (pintype "passive"))
      (node (ref "Q2") (pin "2") (pinfunction "C_2") (pintype "passive"))
      (node (ref "R7") (pin "2") (pinfunction "2_2") (pintype "passive"))
    )
    (net (code "4") (name "/L3") (class "Default")
      (node (ref "DS1") (pin "8") (pinfunction "V3_8") (pintype "passive"))
      (node (ref "Q3") (pin "2") (pinfunction "C_2") (pintype "passive"))
      (node (ref "R8") (pin "2") (pinfunction "2_2") (pintype "passive"))
    )
    (net (code "5") (name "/L4") (class "Default")
      (node (ref "DS1") (pin "6") (pinfunction "V4_6") (pintype "passive"))
      (node (ref "Q4") (pin "2") (pinfunction "C_2") (pintype "passive"))
      (node (ref "R9") (pin "2") (pinfunction "2_2") (pintype "passive"))
    )
    (net (code "6") (name "/NETLIGHT") (class "Default")
      (node (ref "IC3") (pin "41") (pinfunction "NETLIGHT_41") (pintype "output"))
      (node (ref "R31") (pin "1") (pinfunction "1_1") (pintype "passive"))
    )
    (net (code "7") (name "/OSC32_IN") (class "Default")
      (node (ref "C19") (pin "2") (pinfunction "2_2") (pintype "passive"))
      (node (ref "U3") (pin "3") (pinfunction "PC14-OSC32_IN_3") (pintype "passive"))
      (node (ref "Y2") (pin "2") (pinfunction "OSC2_2") (pintype "passive"))
    )
    (net (code "8") (name "/OSC32_OUT") (class "Default")
      (node (ref "C21") (pin "2") (pinfunction "2_2") (pintype "passive"))
      (node (ref "U3") (pin "4") (pinfunction "PC15-OSC32_OUT_4") (pintype "passive"))
      (node (ref "Y2") (pin "1") (pinfunction "OSC1_1") (pintype "passive"))
    )
    (net (code "9") (name "/OSC_IN") (class "Default")
      (node (ref "C17") (pin "2") (pinfunction "2_2") (pintype "passive"))
      (node (ref "U3") (pin "5") (pinfunction "OSC_IN/PD0_5") (pintype "passive"))
      (node (ref "Y1") (pin "2") (pinfunction "OSC2_2") (pintype "passive"))
    )
    (net (code "10") (name "/OSC_OUT") (class "Default")
      (node (ref "C18") (pin "2") (pinfunction "2_2") (pintype "passive"))
      (node (ref "U3") (pin "6") (pinfunction "OSC_OUT/PD1_6") (pintype "passive"))
      (node (ref "Y1") (pin "1") (pinfunction "OSC1_1") (pintype "passive"))
    )
    (net (code "11") (name "/PA0") (class "Default")
      (node (ref "R19") (pin "2") (pinfunction "2_2") (pintype "passive"))
      (node (ref "U3") (pin "14") (pinfunction "PA0-WKUP_14") (pintype "passive"))
    )
    (net (code "12") (name "/PA1") (class "Default")
      (node (ref "R20") (pin "2") (pinfunction "2_2") (pintype "passive"))
      (node (ref "U3") (pin "15") (pinfunction "PA1_15") (pintype "passive"))
    )
    (net (code "13") (name "/PA2") (class "Default")
      (node (ref "R21") (pin "2") (pinfunction "2_2") (pintype "passive"))
      (node (ref "U3") (pin "16") (pinfunction "PA2/USART2_TX/ADC123_IN2_16") (pintype "passive"))
    )
    (net (code "14") (name "/PA3") (class "Default")
      (node (ref "R22") (pin "2") (pinfunction "2_2") (pintype "passive"))
      (node (ref "U3") (pin "17") (pinfunction "PA3/USART2_RX/ADC123_IN3_17") (pintype "passive"))
    )
    (net (code "15") (name "/PA4") (class "Default")
      (node (ref "R23") (pin "2") (pinfunction "2_2") (pintype "passive"))
      (node (ref "U3") (pin "20") (pinfunction "PA4/SPI1_NSS/DAC_OUT1/ADC12_IN4_20") (pintype "passive"))
    )
    (net (code "16") (name "/PA5") (class "Default")
      (node (ref "R24") (pin "2") (pinfunction "2_2") (pintype "passive"))
      (node (ref "U3") (pin "21") (pinfunction "PA5/SPI1_SCK/DAC_OUT2/ADC12_IN5_21") (pintype "passive"))
    )
    (net (code "17") (name "/PA6") (class "Default")
      (node (ref "R25") (pin "2") (pinfunction "2_2") (pintype "passive"))
      (node (ref "U3") (pin "22") (pinfunction "PA6/SPI1_MISO/ADC12_IN6_22") (pintype "passive"))
    )
    (net (code "18") (name "/PA7") (class "Default")
      (node (ref "R26") (pin "2") (pinfunction "2_2") (pintype "passive"))
      (node (ref "U3") (pin "23") (pinfunction "PA7/SPI1_MOSI/ADC12_IN7_23") (pintype "passive"))
    )
    (net (code "19") (name "/PB12") (class "Default")
      (node (ref "R5") (pin "2") (pinfunction "2_2") (pintype "passive"))
      (node (ref "U3") (pin "33") (pinfunction "PB12/SPI2_NSS/I2S2_WS_33") (pintype "passive"))
    )
    (net (code "20") (name "/PB13") (class "Default")
      (node (ref "R10") (pin "2") (pinfunction "2_2") (pintype "passive"))
      (node (ref "U3") (pin "34") (pinfunction "PB13/SPI2_SCK/I2S2_CK/USART3_CTS_34") (pintype "passive"))
    )
    (net (code "21") (name "/PB14") (class "Default")
      (node (ref "R12") (pin "2") (pinfunction "2_2") (pintype "passive"))
      (node (ref "U3") (pin "35") (pinfunction "PB14/SPI2_MISO/USART3_RTS_35") (pintype "passive"))
    )
    (net (code "22") (name "/PB15") (class "Default")
      (node (ref "R17") (pin "2") (pinfunction "2_2") (pintype "passive"))
      (node (ref "U3") (pin "36") (pinfunction "PB15/SPI2_MOSI/I2S2_SD_36") (pintype "passive"))
    )
    (net (code "23") (name "/PC0") (class "Default")
      (node (ref "R1") (pin "2") (pinfunction "2_2") (pintype "passive"))
      (node (ref "U3") (pin "8") (pinfunction "PC0/ADC123_IN10_8") (pintype "passive"))
    )
    (net (code "24") (name "/PC1") (class "Default")
      (node (ref "R2") (pin "2") (pinfunction "2_2") (pintype "passive"))
      (node (ref "U3") (pin "9") (pinfunction "PC1/ADC123_IN11_9") (pintype "passive"))
    )
    (net (code "25") (name "/PC2") (class "Default")
      (node (ref "R3") (pin "2") (pinfunction "2_2") (pintype "passive"))
      (node (ref "U3") (pin "10") (pinfunction "PC2/ADC123_IN12_10") (pintype "passive"))
    )
    (net (code "26") (name "/PC3") (class "Default")
      (node (ref "R4") (pin "2") (pinfunction "2_2") (pintype "passive"))
      (node (ref "U3") (pin "11") (pinfunction "PC3/ADC123_IN13_11") (pintype "passive"))
    )
    (net (code "27") (name "/PC4") (class "Default")
      (node (ref "C23") (pin "2") (pinfunction "2_2") (pintype "passive"))
      (node (ref "R40") (pin "1") (pinfunction "1_1") (pintype "passive"))
      (node (ref "S3") (pin "2") (pinfunction "2_2") (pintype "passive"))
      (node (ref "U3") (pin "24") (pinfunction "PC4/ADC12_IN14_24") (pintype "passive"))
    )
    (net (code "28") (name "/PC5") (class "Default")
      (node (ref "C24") (pin "2") (pinfunction "2_2") (pintype "passive"))
      (node (ref "R41") (pin "1") (pinfunction "1_1") (pintype "passive"))
      (node (ref "S4") (pin "2") (pinfunction "2_2") (pintype "passive"))
      (node (ref "U3") (pin "25") (pinfunction "PC5/ADC12_IN15_25") (pintype "passive"))
    )
    (net (code "29") (name "/PC6") (class "Default")
      (node (ref "C25") (pin "2") (pinfunction "2_2") (pintype "passive"))
      (node (ref "R42") (pin "1") (pinfunction "1_1") (pintype "passive"))
      (node (ref "S5") (pin "2") (pinfunction "2_2") (pintype "passive"))
      (node (ref "U3") (pin "37") (pinfunction "PC6/I2S2_MCK/SDIO_D6_37") (pintype "passive"))
    )
    (net (code "30") (name "/PC7") (class "Default")
      (node (ref "U2") (pin "2") (pinfunction "K_2") (pintype "passive"))
      (node (ref "U3") (pin "38") (pinfunction "PC7/I2S3_MCK/SDIO_D7_38") (pintype "passive"))
    )
    (net (code "31") (name "/PC8") (class "Default")
      (node (ref "U3") (pin "39") (pinfunction "PC8/SDIO_D0_39") (pintype "passive"))
      (node (ref "U4") (pin "2") (pinfunction "K_2") (pintype "passive"))
    )
    (net (code "32") (name "/PC9") (class "Default")
      (node (ref "U3") (pin "40") (pinfunction "PC9/SDIO_D1_40") (pintype "passive"))
      (node (ref "U5") (pin "2") (pinfunction "K_2") (pintype "passive"))
    )
    (net (code "33") (name "/PC10") (class "Default")
      (node (ref "U3") (pin "51") (pinfunction "PC10/UART4_TX/SDIO_D2_51") (pintype "passive"))
      (node (ref "U6") (pin "2") (pinfunction "K_2") (pintype "passive"))
    )
    (net (code "34") (name "/RESET") (class "Default")
      (node (ref "C22") (pin "2") (pinfunction "2_2") (pintype "passive"))
      (node (ref "R39") (pin "1") (pinfunction "1_1") (pintype "passive"))
      (node (ref "S2") (pin "2") (pinfunction "2_2") (pintype "passive"))
      (node (ref "U3") (pin "7") (pinfunction "NRST_7") (pintype "passive"))
    )
    (net (code "35") (name "/RX3") (class "Default")
      (node (ref "GSM1") (pin "2") (pinfunction "2_2") (pintype "passive"))
      (node (ref "IC3") (pin "1") (pinfunction "UART1_TXD_1") (pintype "output"))
      (node (ref "U3") (pin "42") (pinfunction "PA9/USART1_TX_42") (pintype "passive"))
    )
    (net (code "36") (name "/SIM-CLK") (class "Default")
      (node (ref "IC3") (pin "16") (pinfunction "SIM1_CLK_16") (pintype "output"))
      (node (ref "R35") (pin "1") (pinfunction "1_1") (pintype "passive"))
    )
    (net (code "37") (name "/SIM-DATA") (class "Default")
      (node (ref "C20") (pin "1") (pinfunction "1_1") (pintype "passive"))
      (node (ref "IC3") (pin "15") (pinfunction "SIM1_DATA_15") (pintype "bidirectional"))
      (node (ref "R36") (pin "1") (pinfunction "1_1") (pintype "passive"))
    )
    (net (code "38") (name "/SIM-RST") (class "Default")
      (node (ref "IC3") (pin "17") (pinfunction "SIM1_RST_17") (pintype "output"))
      (node (ref "R34") (pin "1") (pinfunction "1_1") (pintype "passive"))
    )
    (net (code "39") (name "/SIM-VDD") (class "Default")
      (node (ref "C16") (pin "1") (pinfunction "1_1") (pintype "passive"))
      (node (ref "IC3") (pin "18") (pinfunction "SIM1_VDD_18") (pintype "output"))
      (node (ref "S1") (pin "1") (pinfunction "VCC_1") (pintype "input"))
    )
    (net (code "40") (name "/STATUS") (class "Default")
      (node (ref "IC3") (pin "42") (pinfunction "STATUS_42") (pintype "output"))
      (node (ref "R30") (pin "1") (pinfunction "1_1") (pintype "passive"))
    )
    (net (code "41") (name "/ST_SWCLK") (class "Default")
      (node (ref "HD1") (pin "2") (pinfunction "2_2") (pintype "passive"))
      (node (ref "U3") (pin "49") (pinfunction "PA14/JTCK/SWCLK_49") (pintype "passive"))
    )
    (net (code "42") (name "/ST_SWDIO") (class "Default")
      (node (ref "HD1") (pin "1") (pinfunction "1_1") (pintype "passive"))
      (node (ref "U3") (pin "46") (pinfunction "PA13/JTMS/SWDIO_46") (pintype "passive"))
    )
    (net (code "43") (name "/TX3") (class "Default")
      (node (ref "GSM1") (pin "1") (pinfunction "1_1") (pintype "passive"))
      (node (ref "IC3") (pin "2") (pinfunction "UART1_RXD_2") (pintype "input"))
      (node (ref "U3") (pin "43") (pinfunction "PA10/USART1_RX_43") (pintype "passive"))
    )
    (net (code "44") (name "3V3") (class "Default")
      (node (ref "C12") (pin "2") (pinfunction "2_2") (pintype "passive"))
      (node (ref "C13") (pin "2") (pinfunction "2_2") (pintype "passive"))
      (node (ref "C14") (pin "2") (pinfunction "2_2") (pintype "passive"))
      (node (ref "C15") (pin "2") (pinfunction "2_2") (pintype "passive"))
      (node (ref "HD1") (pin "3") (pinfunction "3_3") (pintype "passive"))
      (node (ref "IC2") (pin "2") (pinfunction "OUT_2") (pintype "passive"))
      (node (ref "J1") (pin "1") (pinfunction "C1_1") (pintype "passive"))
      (node (ref "J2") (pin "1") (pinfunction "C1_1") (pintype "passive"))
      (node (ref "R39") (pin "2") (pinfunction "2_2") (pintype "passive"))
      (node (ref "R40") (pin "2") (pinfunction "2_2") (pintype "passive"))
      (node (ref "R41") (pin "2") (pinfunction "2_2") (pintype "passive"))
      (node (ref "R42") (pin "2") (pinfunction "2_2") (pintype "passive"))
      (node (ref "U2") (pin "1") (pinfunction "A_1") (pintype "passive"))
      (node (ref "U3") (pin "13") (pinfunction "VDDA_13") (pintype "power_in"))
      (node (ref "U3") (pin "19") (pinfunction "VDD_4_19") (pintype "power_in"))
      (node (ref "U3") (pin "32") (pinfunction "VDD_1_32") (pintype "power_in"))
      (node (ref "U3") (pin "48") (pinfunction "VDD_2_48") (pintype "power_in"))
      (node (ref "U3") (pin "64") (pinfunction "VDD_3_64") (pintype "power_in"))
      (node (ref "U4") (pin "1") (pinfunction "A_1") (pintype "passive"))
      (node (ref "U5") (pin "1") (pinfunction "A_1") (pintype "passive"))
      (node (ref "U6") (pin "1") (pinfunction "A_1") (pintype "passive"))
    )
    (net (code "45") (name "4.4V") (class "Default")
      (node (ref "C10") (pin "1") (pinfunction "1_1") (pintype "passive"))
      (node (ref "C11") (pin "1") (pinfunction "1_1") (pintype "passive"))
      (node (ref "C4") (pin "1") (pinfunction "1_1") (pintype "passive"))
      (node (ref "C6") (pin "2") (pinfunction "2_2") (pintype "passive"))
      (node (ref "C9") (pin "1") (pinfunction "1_1") (pintype "passive"))
      (node (ref "IC2") (pin "3") (pinfunction "IN_3") (pintype "passive"))
      (node (ref "IC3") (pin "34") (pinfunction "VBAT_34") (pintype "input"))
      (node (ref "IC3") (pin "35") (pinfunction "VBAT_35") (pintype "input"))
      (node (ref "L1") (pin "2") (pinfunction "2_2") (pintype "passive"))
      (node (ref "R11") (pin "2") (pinfunction "2_2") (pintype "passive"))
    )
    (net (code "46") (name "4V4") (class "Default")
      (node (ref "R28") (pin "1") (pinfunction "1_1") (pintype "passive"))
      (node (ref "R29") (pin "1") (pinfunction "1_1") (pintype "passive"))
    )
    (net (code "47") (name "5V") (class "Default")
      (node (ref "C1") (pin "1") (pinfunction "1_1") (pintype "passive"))
      (node (ref "D4") (pin "2") (pinfunction "K_2") (pintype "passive"))
      (node (ref "D5") (pin "2") (pinfunction "K_2") (pintype "passive"))
      (node (ref "D6") (pin "2") (pinfunction "K_2") (pintype "passive"))
      (node (ref "D7") (pin "2") (pinfunction "K_2") (pintype "passive"))
      (node (ref "IC1") (pin "3") (pinfunction "OUT_3") (pintype "passive"))
      (node (ref "Q1") (pin "1") (pinfunction "E_1") (pintype "passive"))
      (node (ref "Q2") (pin "1") (pinfunction "E_1") (pintype "passive"))
      (node (ref "Q3") (pin "1") (pinfunction "E_1") (pintype "passive"))
      (node (ref "Q4") (pin "1") (pinfunction "E_1") (pintype "passive"))
      (node (ref "RL1") (pin "1") (pinfunction "1_1") (pintype "passive"))
      (node (ref "RL2") (pin "1") (pinfunction "1_1") (pintype "passive"))
      (node (ref "RL3") (pin "1") (pinfunction "1_1") (pintype "passive"))
      (node (ref "RL4") (pin "1") (pinfunction "1_1") (pintype "passive"))
      (node (ref "U2") (pin "4") (pinfunction "C_4") (pintype "passive"))
      (node (ref "U4") (pin "4") (pinfunction "C_4") (pintype "passive"))
      (node (ref "U5") (pin "4") (pinfunction "C_4") (pintype "passive"))
      (node (ref "U6") (pin "4") (pinfunction "C_4") (pintype "passive"))
    )
    (net (code "48") (name "GND") (class "Default")
      (node (ref "ANT1") (pin "2") (pinfunction "GND_2") (pintype "passive"))
      (node (ref "ANT1") (pin "3") (pinfunction "GND_3") (pintype "passive"))
      (node (ref "ANT1") (pin "4") (pinfunction "GND_4") (pintype "passive"))
      (node (ref "ANT1") (pin "5") (pinfunction "GND_5") (pintype "passive"))
      (node (ref "C1") (pin "2") (pinfunction "2_2") (pintype "passive"))
      (node (ref "C10") (pin "2") (pinfunction "2_2") (pintype "passive"))
      (node (ref "C11") (pin "2") (pinfunction "2_2") (pintype "passive"))
      (node (ref "C12") (pin "1") (pinfunction "1_1") (pintype "passive"))
      (node (ref "C13") (pin "1") (pinfunction "1_1") (pintype "passive"))
      (node (ref "C14") (pin "1") (pinfunction "1_1") (pintype "passive"))
      (node (ref "C15") (pin "1") (pinfunction "1_1") (pintype "passive"))
      (node (ref "C16") (pin "2") (pinfunction "2_2") (pintype "passive"))
      (node (ref "C17") (pin "1") (pinfunction "1_1") (pintype "passive"))
      (node (ref "C18") (pin "1") (pinfunction "1_1") (pintype "passive"))
      (node (ref "C19") (pin "1") (pinfunction "1_1") (pintype "passive"))
      (node (ref "C20") (pin "2") (pinfunction "2_2") (pintype "passive"))
      (node (ref "C21") (pin "1") (pinfunction "1_1") (pintype "passive"))
      (node (ref "C22") (pin "1") (pinfunction "1_1") (pintype "passive"))
      (node (ref "C23") (pin "1") (pinfunction "1_1") (pintype "passive"))
      (node (ref "C24") (pin "1") (pinfunction "1_1") (pintype "passive"))
      (node (ref "C25") (pin "1") (pinfunction "1_1") (pintype "passive"))
      (node (ref "C3") (pin "2") (pinfunction "2_2") (pintype "passive"))
      (node (ref "C4") (pin "2") (pinfunction "2_2") (pintype "passive"))
      (node (ref "C5") (pin "1") (pinfunction "1_1") (pintype "passive"))
      (node (ref "C7") (pin "1") (pinfunction "1_1") (pintype "passive"))
      (node (ref "C8") (pin "1") (pinfunction "1_1") (pintype "passive"))
      (node (ref "C9") (pin "2") (pinfunction "2_2") (pintype "passive"))
      (node (ref "D3") (pin "1") (pinfunction "A_1") (pintype "passive"))
      (node (ref "HD1") (pin "4") (pinfunction "4_4") (pintype "passive"))
      (node (ref "IC1") (pin "2") (pinfunction "GND_2") (pintype "passive"))
      (node (ref "IC2") (pin "1") (pinfunction "ADJ/G_1") (pintype "passive"))
      (node (ref "IC3") (pin "13") (pinfunction "GND_13") (pintype "power_in"))
      (node (ref "IC3") (pin "19") (pinfunction "GND_19") (pintype "power_in"))
      (node (ref "IC3") (pin "21") (pinfunction "GND_21") (pintype "power_in"))
      (node (ref "IC3") (pin "27") (pinfunction "GND_27") (pintype "power_in"))
      (node (ref "IC3") (pin "30") (pinfunction "GND_30") (pintype "power_in"))
      (node (ref "IC3") (pin "31") (pinfunction "GND_31") (pintype "power_in"))
      (node (ref "IC3") (pin "33") (pinfunction "GND_33") (pintype "power_in"))
      (node (ref "IC3") (pin "36") (pinfunction "GND_36") (pintype "power_in"))
      (node (ref "IC3") (pin "37") (pinfunction "GND_37") (pintype "power_in"))
      (node (ref "IC3") (pin "8") (pinfunction "GND_8") (pintype "power_in"))
      (node (ref "JDC1") (pin "2") (pinfunction "TN_2") (pintype "passive"))
      (node (ref "JDC1") (pin "3") (pinfunction "S_3") (pintype "power_in"))
      (node (ref "LED1") (pin "2") (pinfunction "K_2") (pintype "passive"))
      (node (ref "LED2") (pin "2") (pinfunction "K_2") (pintype "passive"))
      (node (ref "LED3") (pin "2") (pinfunction "K_2") (pintype "passive"))
      (node (ref "LED4") (pin "2") (pinfunction "K_2") (pintype "passive"))
      (node (ref "Q10") (pin "1") (pinfunction "E_1") (pintype "passive"))
      (node (ref "Q5") (pin "1") (pinfunction "E_1") (pintype "passive"))
      (node (ref "Q6") (pin "1") (pinfunction "E_1") (pintype "passive"))
      (node (ref "Q7") (pin "1") (pinfunction "E_1") (pintype "passive"))
      (node (ref "Q8") (pin "1") (pinfunction "E_1") (pintype "passive"))
      (node (ref "Q9") (pin "1") (pinfunction "E_1") (pintype "passive"))
      (node (ref "R15") (pin "1") (pinfunction "1_1") (pintype "passive"))
      (node (ref "R16") (pin "1") (pinfunction "1_1") (pintype "passive"))
      (node (ref "R18") (pin "2") (pinfunction "2_2") (pintype "passive"))
      (node (ref "R27") (pin "2") (pinfunction "2_2") (pintype "passive"))
      (node (ref "R32") (pin "2") (pinfunction "2_2") (pintype "passive"))
      (node (ref "R33") (pin "2") (pinfunction "2_2") (pintype "passive"))
      (node (ref "R37") (pin "2") (pinfunction "2_2") (pintype "passive"))
      (node (ref "R38") (pin "2") (pinfunction "2_2") (pintype "passive"))
      (node (ref "R6") (pin "1") (pinfunction "1_1") (pintype "passive"))
      (node (ref "R7") (pin "1") (pinfunction "1_1") (pintype "passive"))
      (node (ref "R8") (pin "1") (pinfunction "1_1") (pintype "passive"))
      (node (ref "R9") (pin "1") (pinfunction "1_1") (pintype "passive"))
      (node (ref "S1") (pin "5") (pinfunction "GND_5") (pintype "passive"))
      (node (ref "S2") (pin "1") (pinfunction "1_1") (pintype "passive"))
      (node (ref "S3") (pin "1") (pinfunction "1_1") (pintype "passive"))
      (node (ref "S4") (pin "1") (pinfunction "1_1") (pintype "passive"))
      (node (ref "S5") (pin "1") (pinfunction "1_1") (pintype "passive"))
      (node (ref "U1") (pin "7") (pinfunction "GND_7") (pintype "passive"))
      (node (ref "U1") (pin "9") (pinfunction "GND_PAD_9") (pintype "passive"))
      (node (ref "U3") (pin "12") (pinfunction "VSSA_12") (pintype "power_in"))
      (node (ref "U3") (pin "18") (pinfunction "VSS_4_18") (pintype "power_in"))
      (node (ref "U3") (pin "31") (pinfunction "VSS_1_31") (pintype "power_in"))
      (node (ref "U3") (pin "47") (pinfunction "VSS_2_47") (pintype "power_in"))
      (node (ref "U3") (pin "63") (pinfunction "VSS_3_63") (pintype "power_in"))
    )
    (net (code "49") (name "Net-(ANT1-ANT)") (class "Default")
      (node (ref "ANT1") (pin "1") (pinfunction "ANT_1") (pintype "passive"))
      (node (ref "IC3") (pin "32") (pinfunction "GSM_ANT_32") (pintype "bidirectional"))
    )
    (net (code "50") (name "Net-(C8-Pad2)") (class "Default")
      (node (ref "C8") (pin "2") (pinfunction "2_2") (pintype "passive"))
      (node (ref "R14") (pin "1") (pinfunction "1_1") (pintype "passive"))
    )
    (net (code "51") (name "Net-(D1-K)") (class "Default")
      (node (ref "C2") (pin "2") (pinfunction "2_2") (pintype "passive"))
      (node (ref "D1") (pin "2") (pinfunction "K_2") (pintype "passive"))
      (node (ref "L1") (pin "1") (pinfunction "1_1") (pintype "passive"))
      (node (ref "U1") (pin "8") (pinfunction "SW_8") (pintype "passive"))
    )
    (net (code "52") (name "Net-(D2-K)") (class "Default")
      (node (ref "D2") (pin "2") (pinfunction "K_2") (pintype "passive"))
      (node (ref "F1") (pin "1") (pinfunction "1_1") (pintype "passive"))
    )
    (net (code "53") (name "Net-(D3-K)") (class "Default")
      (node (ref "D3") (pin "2") (pinfunction "K_2") (pintype "passive"))
      (node (ref "F1") (pin "2") (pinfunction "2_2") (pintype "passive"))
      (node (ref "L2") (pin "1") (pinfunction "1_1") (pintype "passive"))
    )
    (net (code "54") (name "Net-(D4-A)") (class "Default")
      (node (ref "D4") (pin "1") (pinfunction "A_1") (pintype "passive"))
      (node (ref "Q7") (pin "2") (pinfunction "C_2") (pintype "passive"))
      (node (ref "RL1") (pin "2") (pinfunction "2_2") (pintype "passive"))
    )
    (net (code "55") (name "Net-(D5-A)") (class "Default")
      (node (ref "D5") (pin "1") (pinfunction "A_1") (pintype "passive"))
      (node (ref "Q8") (pin "2") (pinfunction "C_2") (pintype "passive"))
      (node (ref "RL2") (pin "2") (pinfunction "2_2") (pintype "passive"))
    )
    (net (code "56") (name "Net-(D6-A)") (class "Default")
      (node (ref "D6") (pin "1") (pinfunction "A_1") (pintype "passive"))
      (node (ref "Q9") (pin "2") (pinfunction "C_2") (pintype "passive"))
      (node (ref "RL3") (pin "2") (pinfunction "2_2") (pintype "passive"))
    )
    (net (code "57") (name "Net-(D7-A)") (class "Default")
      (node (ref "D7") (pin "1") (pinfunction "A_1") (pintype "passive"))
      (node (ref "Q10") (pin "2") (pinfunction "C_2") (pintype "passive"))
      (node (ref "RL4") (pin "2") (pinfunction "2_2") (pintype "passive"))
    )
    (net (code "58") (name "Net-(DS1-a)") (class "Default")
      (node (ref "DS1") (pin "11") (pinfunction "a_11") (pintype "passive"))
      (node (ref "R19") (pin "1") (pinfunction "1_1") (pintype "passive"))
    )
    (net (code "59") (name "Net-(DS1-b)") (class "Default")
      (node (ref "DS1") (pin "7") (pinfunction "b_7") (pintype "passive"))
      (node (ref "R20") (pin "1") (pinfunction "1_1") (pintype "passive"))
    )
    (net (code "60") (name "Net-(DS1-c)") (class "Default")
      (node (ref "DS1") (pin "4") (pinfunction "c_4") (pintype "passive"))
      (node (ref "R21") (pin "1") (pinfunction "1_1") (pintype "passive"))
    )
    (net (code "61") (name "Net-(DS1-d)") (class "Default")
      (node (ref "DS1") (pin "2") (pinfunction "d_2") (pintype "passive"))
      (node (ref "R22") (pin "1") (pinfunction "1_1") (pintype "passive"))
    )
    (net (code "62") (name "Net-(DS1-e)") (class "Default")
      (node (ref "DS1") (pin "1") (pinfunction "e_1") (pintype "passive"))
      (node (ref "R23") (pin "1") (pinfunction "1_1") (pintype "passive"))
    )
    (net (code "63") (name "Net-(DS1-f)") (class "Default")
      (node (ref "DS1") (pin "10") (pinfunction "f_10") (pintype "passive"))
      (node (ref "R24") (pin "1") (pinfunction "1_1") (pintype "passive"))
    )
    (net (code "64") (name "Net-(DS1-g)") (class "Default")
      (node (ref "DS1") (pin "5") (pinfunction "g_5") (pintype "passive"))
      (node (ref "R25") (pin "1") (pinfunction "1_1") (pintype "passive"))
    )
    (net (code "65") (name "Net-(DS1-h)") (class "Default")
      (node (ref "DS1") (pin "3") (pinfunction "h_3") (pintype "passive"))
      (node (ref "R26") (pin "1") (pinfunction "1_1") (pintype "passive"))
    )
    (net (code "66") (name "Net-(IC1-IN)") (class "Default")
      (node (ref "C3") (pin "1") (pinfunction "1_1") (pintype "passive"))
      (node (ref "C5") (pin "2") (pinfunction "2_2") (pintype "passive"))
      (node (ref "IC1") (pin "1") (pinfunction "IN_1") (pintype "passive"))
      (node (ref "L2") (pin "2") (pinfunction "2_2") (pintype "passive"))
      (node (ref "R13") (pin "2") (pinfunction "2_2") (pintype "passive"))
      (node (ref "U1") (pin "2") (pinfunction "VIN_2") (pintype "passive"))
    )
    (net (code "67") (name "Net-(IC3-PWRKEY)") (class "Default")
      (node (ref "IC3") (pin "39") (pinfunction "PWRKEY_39") (pintype "input"))
      (node (ref "R27") (pin "1") (pinfunction "1_1") (pintype "passive"))
    )
    (net (code "68") (name "Net-(J1-C2)") (class "Default")
      (node (ref "J1") (pin "2") (pinfunction "C2_2") (pintype "passive"))
      (node (ref "R37") (pin "1") (pinfunction "1_1") (pintype "passive"))
      (node (ref "U3") (pin "28") (pinfunction "PB2/BOOT1_28") (pintype "passive"))
    )
    (net (code "69") (name "Net-(J2-C2)") (class "Default")
      (node (ref "J2") (pin "2") (pinfunction "C2_2") (pintype "passive"))
      (node (ref "R38") (pin "1") (pinfunction "1_1") (pintype "passive"))
      (node (ref "U3") (pin "60") (pinfunction "BOOT0_60") (pintype "passive"))
    )
    (net (code "70") (name "Net-(JP1-Pad1)") (class "Default")
      (node (ref "JP1") (pin "1") (pinfunction "1_1") (pintype "passive"))
      (node (ref "RL1") (pin "3") (pinfunction "3_3") (pintype "passive"))
      (node (ref "RL2") (pin "3") (pinfunction "3_3") (pintype "passive"))
      (node (ref "RL3") (pin "3") (pinfunction "3_3") (pintype "passive"))
      (node (ref "RL4") (pin "3") (pinfunction "3_3") (pintype "passive"))
    )
    (net (code "71") (name "Net-(JP1-Pad2)") (class "Default")
      (node (ref "JP1") (pin "2") (pinfunction "2_2") (pintype "passive"))
      (node (ref "JP2") (pin "1") (pinfunction "1_1") (pintype "passive"))
      (node (ref "JP3") (pin "1") (pinfunction "1_1") (pintype "passive"))
      (node (ref "JP4") (pin "1") (pinfunction "1_1") (pintype "passive"))
      (node (ref "JP5") (pin "1") (pinfunction "1_1") (pintype "passive"))
    )
    (net (code "72") (name "Net-(JP2-Pad2)") (class "Default")
      (node (ref "JP2") (pin "2") (pinfunction "2_2") (pintype "passive"))
      (node (ref "RL1") (pin "5") (pinfunction "5_5") (pintype "passive"))
    )
    (net (code "73") (name "Net-(JP3-Pad2)") (class "Default")
      (node (ref "JP3") (pin "2") (pinfunction "2_2") (pintype "passive"))
      (node (ref "RL2") (pin "5") (pinfunction "5_5") (pintype "passive"))
    )
    (net (code "74") (name "Net-(JP4-Pad2)") (class "Default")
      (node (ref "JP4") (pin "2") (pinfunction "2_2") (pintype "passive"))
      (node (ref "RL3") (pin "5") (pinfunction "5_5") (pintype "passive"))
    )
    (net (code "75") (name "Net-(JP5-Pad2)") (class "Default")
      (node (ref "JP5") (pin "2") (pinfunction "2_2") (pintype "passive"))
      (node (ref "RL4") (pin "5") (pinfunction "5_5") (pintype "passive"))
    )
    (net (code "76") (name "Net-(LED1-A)") (class "Default")
      (node (ref "LED1") (pin "1") (pinfunction "A_1") (pintype "passive"))
      (node (ref "R5") (pin "1") (pinfunction "1_1") (pintype "passive"))
    )
    (net (code "77") (name "Net-(LED2-A)") (class "Default")
      (node (ref "LED2") (pin "1") (pinfunction "A_1") (pintype "passive"))
      (node (ref "R10") (pin "1") (pinfunction "1_1") (pintype "passive"))
    )
    (net (code "78") (name "Net-(LED3-A)") (class "Default")
      (node (ref "LED3") (pin "1") (pinfunction "A_1") (pintype "passive"))
      (node (ref "R12") (pin "1") (pinfunction "1_1") (pintype "passive"))
    )
    (net (code "79") (name "Net-(LED4-A)") (class "Default")
      (node (ref "LED4") (pin "1") (pinfunction "A_1") (pintype "passive"))
      (node (ref "R17") (pin "1") (pinfunction "1_1") (pintype "passive"))
    )
    (net (code "80") (name "Net-(LED5-A)") (class "Default")
      (node (ref "LED5") (pin "1") (pinfunction "A_1") (pintype "passive"))
      (node (ref "R28") (pin "2") (pinfunction "2_2") (pintype "passive"))
    )
    (net (code "81") (name "Net-(LED5-K)") (class "Default")
      (node (ref "LED5") (pin "2") (pinfunction "K_2") (pintype "passive"))
      (node (ref "Q5") (pin "2") (pinfunction "C_2") (pintype "passive"))
    )
    (net (code "82") (name "Net-(LED6-A)") (class "Default")
      (node (ref "LED6") (pin "1") (pinfunction "A_1") (pintype "passive"))
      (node (ref "R29") (pin "2") (pinfunction "2_2") (pintype "passive"))
    )
    (net (code "83") (name "Net-(LED6-K)") (class "Default")
      (node (ref "LED6") (pin "2") (pinfunction "K_2") (pintype "passive"))
      (node (ref "Q6") (pin "2") (pinfunction "C_2") (pintype "passive"))
    )
    (net (code "84") (name "Net-(Q1-B)") (class "Default")
      (node (ref "Q1") (pin "3") (pinfunction "B_3") (pintype "passive"))
      (node (ref "R1") (pin "1") (pinfunction "1_1") (pintype "passive"))
    )
    (net (code "85") (name "Net-(Q2-B)") (class "Default")
      (node (ref "Q2") (pin "3") (pinfunction "B_3") (pintype "passive"))
      (node (ref "R2") (pin "1") (pinfunction "1_1") (pintype "passive"))
    )
    (net (code "86") (name "Net-(Q3-B)") (class "Default")
      (node (ref "Q3") (pin "3") (pinfunction "B_3") (pintype "passive"))
      (node (ref "R3") (pin "1") (pinfunction "1_1") (pintype "passive"))
    )
    (net (code "87") (name "Net-(Q4-B)") (class "Default")
      (node (ref "Q4") (pin "3") (pinfunction "B_3") (pintype "passive"))
      (node (ref "R4") (pin "1") (pinfunction "1_1") (pintype "passive"))
    )
    (net (code "88") (name "Net-(Q5-B)") (class "Default")
      (node (ref "Q5") (pin "3") (pinfunction "B_3") (pintype "passive"))
      (node (ref "R30") (pin "2") (pinfunction "2_2") (pintype "passive"))
      (node (ref "R32") (pin "1") (pinfunction "1_1") (pintype "passive"))
    )
    (net (code "89") (name "Net-(Q6-B)") (class "Default")
      (node (ref "Q6") (pin "3") (pinfunction "B_3") (pintype "passive"))
      (node (ref "R31") (pin "2") (pinfunction "2_2") (pintype "passive"))
      (node (ref "R33") (pin "1") (pinfunction "1_1") (pintype "passive"))
    )
    (net (code "90") (name "Net-(Q7-B)") (class "Default")
      (node (ref "Q7") (pin "3") (pinfunction "B_3") (pintype "passive"))
      (node (ref "U2") (pin "3") (pinfunction "E_3") (pintype "passive"))
    )
    (net (code "91") (name "Net-(Q8-B)") (class "Default")
      (node (ref "Q8") (pin "3") (pinfunction "B_3") (pintype "passive"))
      (node (ref "U4") (pin "3") (pinfunction "E_3") (pintype "passive"))
    )
    (net (code "92") (name "Net-(Q9-B)") (class "Default")
      (node (ref "Q9") (pin "3") (pinfunction "B_3") (pintype "passive"))
      (node (ref "U5") (pin "3") (pinfunction "E_3") (pintype "passive"))
    )
    (net (code "93") (name "Net-(Q10-B)") (class "Default")
      (node (ref "Q10") (pin "3") (pinfunction "B_3") (pintype "passive"))
      (node (ref "U6") (pin "3") (pinfunction "E_3") (pintype "passive"))
    )
    (net (code "94") (name "Net-(S1-CLK)") (class "Default")
      (node (ref "R35") (pin "2") (pinfunction "2_2") (pintype "passive"))
      (node (ref "S1") (pin "3") (pinfunction "CLK_3") (pintype "input"))
    )
    (net (code "95") (name "Net-(S1-I{slash}O)") (class "Default")
      (node (ref "R36") (pin "2") (pinfunction "2_2") (pintype "passive"))
      (node (ref "S1") (pin "7") (pinfunction "I/O_7") (pintype "bidirectional"))
    )
    (net (code "96") (name "Net-(S1-RST)") (class "Default")
      (node (ref "R34") (pin "2") (pinfunction "2_2") (pintype "passive"))
      (node (ref "S1") (pin "2") (pinfunction "RST_2") (pintype "input"))
    )
    (net (code "97") (name "Net-(U1-BOOT)") (class "Default")
      (node (ref "C2") (pin "1") (pinfunction "1_1") (pintype "passive"))
      (node (ref "U1") (pin "1") (pinfunction "BOOT_1") (pintype "passive"))
    )
    (net (code "98") (name "Net-(U1-COMP)") (class "Default")
      (node (ref "C7") (pin "2") (pinfunction "2_2") (pintype "passive"))
      (node (ref "R14") (pin "2") (pinfunction "2_2") (pintype "passive"))
      (node (ref "U1") (pin "6") (pinfunction "COMP_6") (pintype "passive"))
    )
    (net (code "99") (name "Net-(U1-EN)") (class "Default")
      (node (ref "R13") (pin "1") (pinfunction "1_1") (pintype "passive"))
      (node (ref "R16") (pin "2") (pinfunction "2_2") (pintype "passive"))
      (node (ref "U1") (pin "3") (pinfunction "EN_3") (pintype "passive"))
    )
    (net (code "100") (name "Net-(U1-FB)") (class "Default")
      (node (ref "R11") (pin "1") (pinfunction "1_1") (pintype "passive"))
      (node (ref "R15") (pin "2") (pinfunction "2_2") (pintype "passive"))
      (node (ref "U1") (pin "5") (pinfunction "FB_5") (pintype "passive"))
    )
    (net (code "101") (name "Net-(U1-RT{slash}CLK)") (class "Default")
      (node (ref "R18") (pin "1") (pinfunction "1_1") (pintype "passive"))
      (node (ref "U1") (pin "4") (pinfunction "RT/CLK_4") (pintype "passive"))
    )
    (net (code "102") (name "PGND") (class "Default")
      (node (ref "C6") (pin "1") (pinfunction "1_1") (pintype "passive"))
      (node (ref "D1") (pin "1") (pinfunction "A_1") (pintype "passive"))
    )
    (net (code "103") (name "V_In") (class "Default")
      (node (ref "D2") (pin "1") (pinfunction "A_1") (pintype "passive"))
      (node (ref "JDC1") (pin "1") (pinfunction "T_1") (pintype "passive"))
    )
    (net (code "104") (name "unconnected-(IC2-Tab-Pad4)") (class "Default")
      (node (ref "IC2") (pin "4") (pinfunction "Tab_4") (pintype "passive+no_connect"))
    )
    (net (code "105") (name "unconnected-(IC3-ADC-Pad38)") (class "Default")
      (node (ref "IC3") (pin "38") (pinfunction "ADC_38") (pintype "input+no_connect"))
    )
    (net (code "106") (name "unconnected-(IC3-BT_ANT-Pad20)") (class "Default")
      (node (ref "IC3") (pin "20") (pinfunction "BT_ANT_20") (pintype "bidirectional+no_connect"))
    )
    (net (code "107") (name "unconnected-(IC3-MICN-Pad10)") (class "Default")
      (node (ref "IC3") (pin "10") (pinfunction "MICN_10") (pintype "input+no_connect"))
    )
    (net (code "108") (name "unconnected-(IC3-MICP-Pad9)") (class "Default")
      (node (ref "IC3") (pin "9") (pinfunction "MICP_9") (pintype "input+no_connect"))
    )
    (net (code "109") (name "unconnected-(IC3-RF_SYNC-Pad29)") (class "Default")
      (node (ref "IC3") (pin "29") (pinfunction "RF_SYNC_29") (pintype "output+no_connect"))
    )
    (net (code "110") (name "unconnected-(IC3-SIM1_DET-Pad14)") (class "Default")
      (node (ref "IC3") (pin "14") (pinfunction "SIM1_DET_14") (pintype "input+no_connect"))
    )
    (net (code "111") (name "unconnected-(IC3-SPKN-Pad12)") (class "Default")
      (node (ref "IC3") (pin "12") (pinfunction "SPKN_12") (pintype "output+no_connect"))
    )
    (net (code "112") (name "unconnected-(IC3-SPKP-Pad11)") (class "Default")
      (node (ref "IC3") (pin "11") (pinfunction "SPKP_11") (pintype "output+no_connect"))
    )
    (net (code "113") (name "unconnected-(IC3-UART1_CTS-Pad4)") (class "Default")
      (node (ref "IC3") (pin "4") (pinfunction "UART1_CTS_4") (pintype "output+no_connect"))
    )
    (net (code "114") (name "unconnected-(IC3-UART1_DCD-Pad5)") (class "Default")
      (node (ref "IC3") (pin "5") (pinfunction "UART1_DCD_5") (pintype "output+no_connect"))
    )
    (net (code "115") (name "unconnected-(IC3-UART1_DTR-Pad6)") (class "Default")
      (node (ref "IC3") (pin "6") (pinfunction "UART1_DTR_6") (pintype "input+no_connect"))
    )
    (net (code "116") (name "unconnected-(IC3-UART1_RI-Pad7)") (class "Default")
      (node (ref "IC3") (pin "7") (pinfunction "UART1_RI_7") (pintype "output+no_connect"))
    )
    (net (code "117") (name "unconnected-(IC3-UART1_RST-Pad3)") (class "Default")
      (node (ref "IC3") (pin "3") (pinfunction "UART1_RST_3") (pintype "input+no_connect"))
    )
    (net (code "118") (name "unconnected-(IC3-UART2_RXD-Pad23)") (class "Default")
      (node (ref "IC3") (pin "23") (pinfunction "UART2_RXD_23") (pintype "input+no_connect"))
    )
    (net (code "119") (name "unconnected-(IC3-UART2_TXD-Pad22)") (class "Default")
      (node (ref "IC3") (pin "22") (pinfunction "UART2_TXD_22") (pintype "output+no_connect"))
    )
    (net (code "120") (name "unconnected-(IC3-USB_DM-Pad26)") (class "Default")
      (node (ref "IC3") (pin "26") (pinfunction "USB_DM_26") (pintype "bidirectional+no_connect"))
    )
    (net (code "121") (name "unconnected-(IC3-USB_DP-Pad25)") (class "Default")
      (node (ref "IC3") (pin "25") (pinfunction "USB_DP_25") (pintype "bidirectional+no_connect"))
    )
    (net (code "122") (name "unconnected-(IC3-USB_VBUS-Pad24)") (class "Default")
      (node (ref "IC3") (pin "24") (pinfunction "USB_VBUS_24") (pintype "input+no_connect"))
    )
    (net (code "123") (name "unconnected-(IC3-VDD_EXT-Pad40)") (class "Default")
      (node (ref "IC3") (pin "40") (pinfunction "VDD_EXT_40") (pintype "output+no_connect"))
    )
    (net (code "124") (name "unconnected-(IC3-VRTC-Pad28)") (class "Default")
      (node (ref "IC3") (pin "28") (pinfunction "VRTC_28") (pintype "passive+no_connect"))
    )
    (net (code "125") (name "unconnected-(RL1-Pad4)") (class "Default")
      (node (ref "RL1") (pin "4") (pinfunction "4_4") (pintype "passive+no_connect"))
    )
    (net (code "126") (name "unconnected-(RL2-Pad4)") (class "Default")
      (node (ref "RL2") (pin "4") (pinfunction "4_4") (pintype "passive+no_connect"))
    )
    (net (code "127") (name "unconnected-(RL3-Pad4)") (class "Default")
      (node (ref "RL3") (pin "4") (pinfunction "4_4") (pintype "passive+no_connect"))
    )
    (net (code "128") (name "unconnected-(RL4-Pad4)") (class "Default")
      (node (ref "RL4") (pin "4") (pinfunction "4_4") (pintype "passive+no_connect"))
    )
    (net (code "129") (name "unconnected-(S1-VPP-Pad6)") (class "Default")
      (node (ref "S1") (pin "6") (pinfunction "VPP_6") (pintype "passive+no_connect"))
    )
    (net (code "130") (name "unconnected-(U3-PA8-Pad41)") (class "Default")
      (node (ref "U3") (pin "41") (pinfunction "PA8_41") (pintype "passive+no_connect"))
    )
    (net (code "131") (name "unconnected-(U3-PA11{slash}USART1_CTS{slash}USBDM{slash}CAN_RX-Pad44)") (class "Default")
      (node (ref "U3") (pin "44") (pinfunction "PA11/USART1_CTS/USBDM/CAN_RX_44") (pintype "passive+no_connect"))
    )
    (net (code "132") (name "unconnected-(U3-PA12{slash}USART1_RTS{slash}USBDP{slash}CAN_TX-Pad45)") (class "Default")
      (node (ref "U3") (pin "45") (pinfunction "PA12/USART1_RTS/USBDP/CAN_TX_45") (pintype "passive+no_connect"))
    )
    (net (code "133") (name "unconnected-(U3-PA15{slash}JTDI-Pad50)") (class "Default")
      (node (ref "U3") (pin "50") (pinfunction "PA15/JTDI_50") (pintype "passive+no_connect"))
    )
    (net (code "134") (name "unconnected-(U3-PB0{slash}ADC12_IN8-Pad26)") (class "Default")
      (node (ref "U3") (pin "26") (pinfunction "PB0/ADC12_IN8_26") (pintype "passive+no_connect"))
    )
    (net (code "135") (name "unconnected-(U3-PB1{slash}ADC12_IN9-Pad27)") (class "Default")
      (node (ref "U3") (pin "27") (pinfunction "PB1/ADC12_IN9_27") (pintype "passive+no_connect"))
    )
    (net (code "136") (name "unconnected-(U3-PB3{slash}JTDO-Pad55)") (class "Default")
      (node (ref "U3") (pin "55") (pinfunction "PB3/JTDO_55") (pintype "passive+no_connect"))
    )
    (net (code "137") (name "unconnected-(U3-PB4{slash}JNTRST-Pad56)") (class "Default")
      (node (ref "U3") (pin "56") (pinfunction "PB4/JNTRST_56") (pintype "passive+no_connect"))
    )
    (net (code "138") (name "unconnected-(U3-PB5{slash}SPI3_MOSI{slash}SPI1_MOSI-Pad57)") (class "Default")
      (node (ref "U3") (pin "57") (pinfunction "PB5/SPI3_MOSI/SPI1_MOSI_57") (pintype "passive+no_connect"))
    )
    (net (code "139") (name "unconnected-(U3-PB6{slash}I2C1_SCL{slash}USART1_TX-Pad58)") (class "Default")
      (node (ref "U3") (pin "58") (pinfunction "PB6/I2C1_SCL/USART1_TX_58") (pintype "passive+no_connect"))
    )
    (net (code "140") (name "unconnected-(U3-PB7{slash}I2C1_SDA{slash}USART1_RX-Pad59)") (class "Default")
      (node (ref "U3") (pin "59") (pinfunction "PB7/I2C1_SDA/USART1_RX_59") (pintype "passive+no_connect"))
    )
    (net (code "141") (name "unconnected-(U3-PB8{slash}SDIO_D4{slash}I2C1_SCL{slash}CAN_RX-Pad61)") (class "Default")
      (node (ref "U3") (pin "61") (pinfunction "PB8/SDIO_D4/I2C1_SCL/CAN_RX_61") (pintype "passive+no_connect"))
    )
    (net (code "142") (name "unconnected-(U3-PB9{slash}SDIO_D5{slash}I2C1_SDA{slash}CAN_TX-Pad62)") (class "Default")
      (node (ref "U3") (pin "62") (pinfunction "PB9/SDIO_D5/I2C1_SDA/CAN_TX_62") (pintype "passive+no_connect"))
    )
    (net (code "143") (name "unconnected-(U3-PB10{slash}I2C2_SCL{slash}USART3_TX-Pad29)") (class "Default")
      (node (ref "U3") (pin "29") (pinfunction "PB10/I2C2_SCL/USART3_TX_29") (pintype "passive+no_connect"))
    )
    (net (code "144") (name "unconnected-(U3-PB11{slash}I2C2_SDA{slash}USART3_RX-Pad30)") (class "Default")
      (node (ref "U3") (pin "30") (pinfunction "PB11/I2C2_SDA/USART3_RX_30") (pintype "passive+no_connect"))
    )
    (net (code "145") (name "unconnected-(U3-PC11{slash}UART4_RX{slash}SDIO_D3-Pad52)") (class "Default")
      (node (ref "U3") (pin "52") (pinfunction "PC11/UART4_RX/SDIO_D3_52") (pintype "passive+no_connect"))
    )
    (net (code "146") (name "unconnected-(U3-PC12{slash}UART5_TX{slash}SDIO_CK-Pad53)") (class "Default")
      (node (ref "U3") (pin "53") (pinfunction "PC12/UART5_TX/SDIO_CK_53") (pintype "passive+no_connect"))
    )
    (net (code "147") (name "unconnected-(U3-PC13-TAMPER-RTC-Pad2)") (class "Default")
      (node (ref "U3") (pin "2") (pinfunction "PC13-TAMPER-RTC_2") (pintype "passive+no_connect"))
    )
    (net (code "148") (name "unconnected-(U3-PD2{slash}UART5_RX{slash}SDIO_CMD-Pad54)") (class "Default")
      (node (ref "U3") (pin "54") (pinfunction "PD2/UART5_RX/SDIO_CMD_54") (pintype "passive+no_connect"))
    )
    (net (code "149") (name "unconnected-(U3-VBAT-Pad1)") (class "Default")
      (node (ref "U3") (pin "1") (pinfunction "VBAT_1") (pintype "power_in"))
    )
  )
)
